# ProPrj_arm_can_tool_2026-04-18.net
KiCad netlist of a schematic drawn in EasyEDA Pro
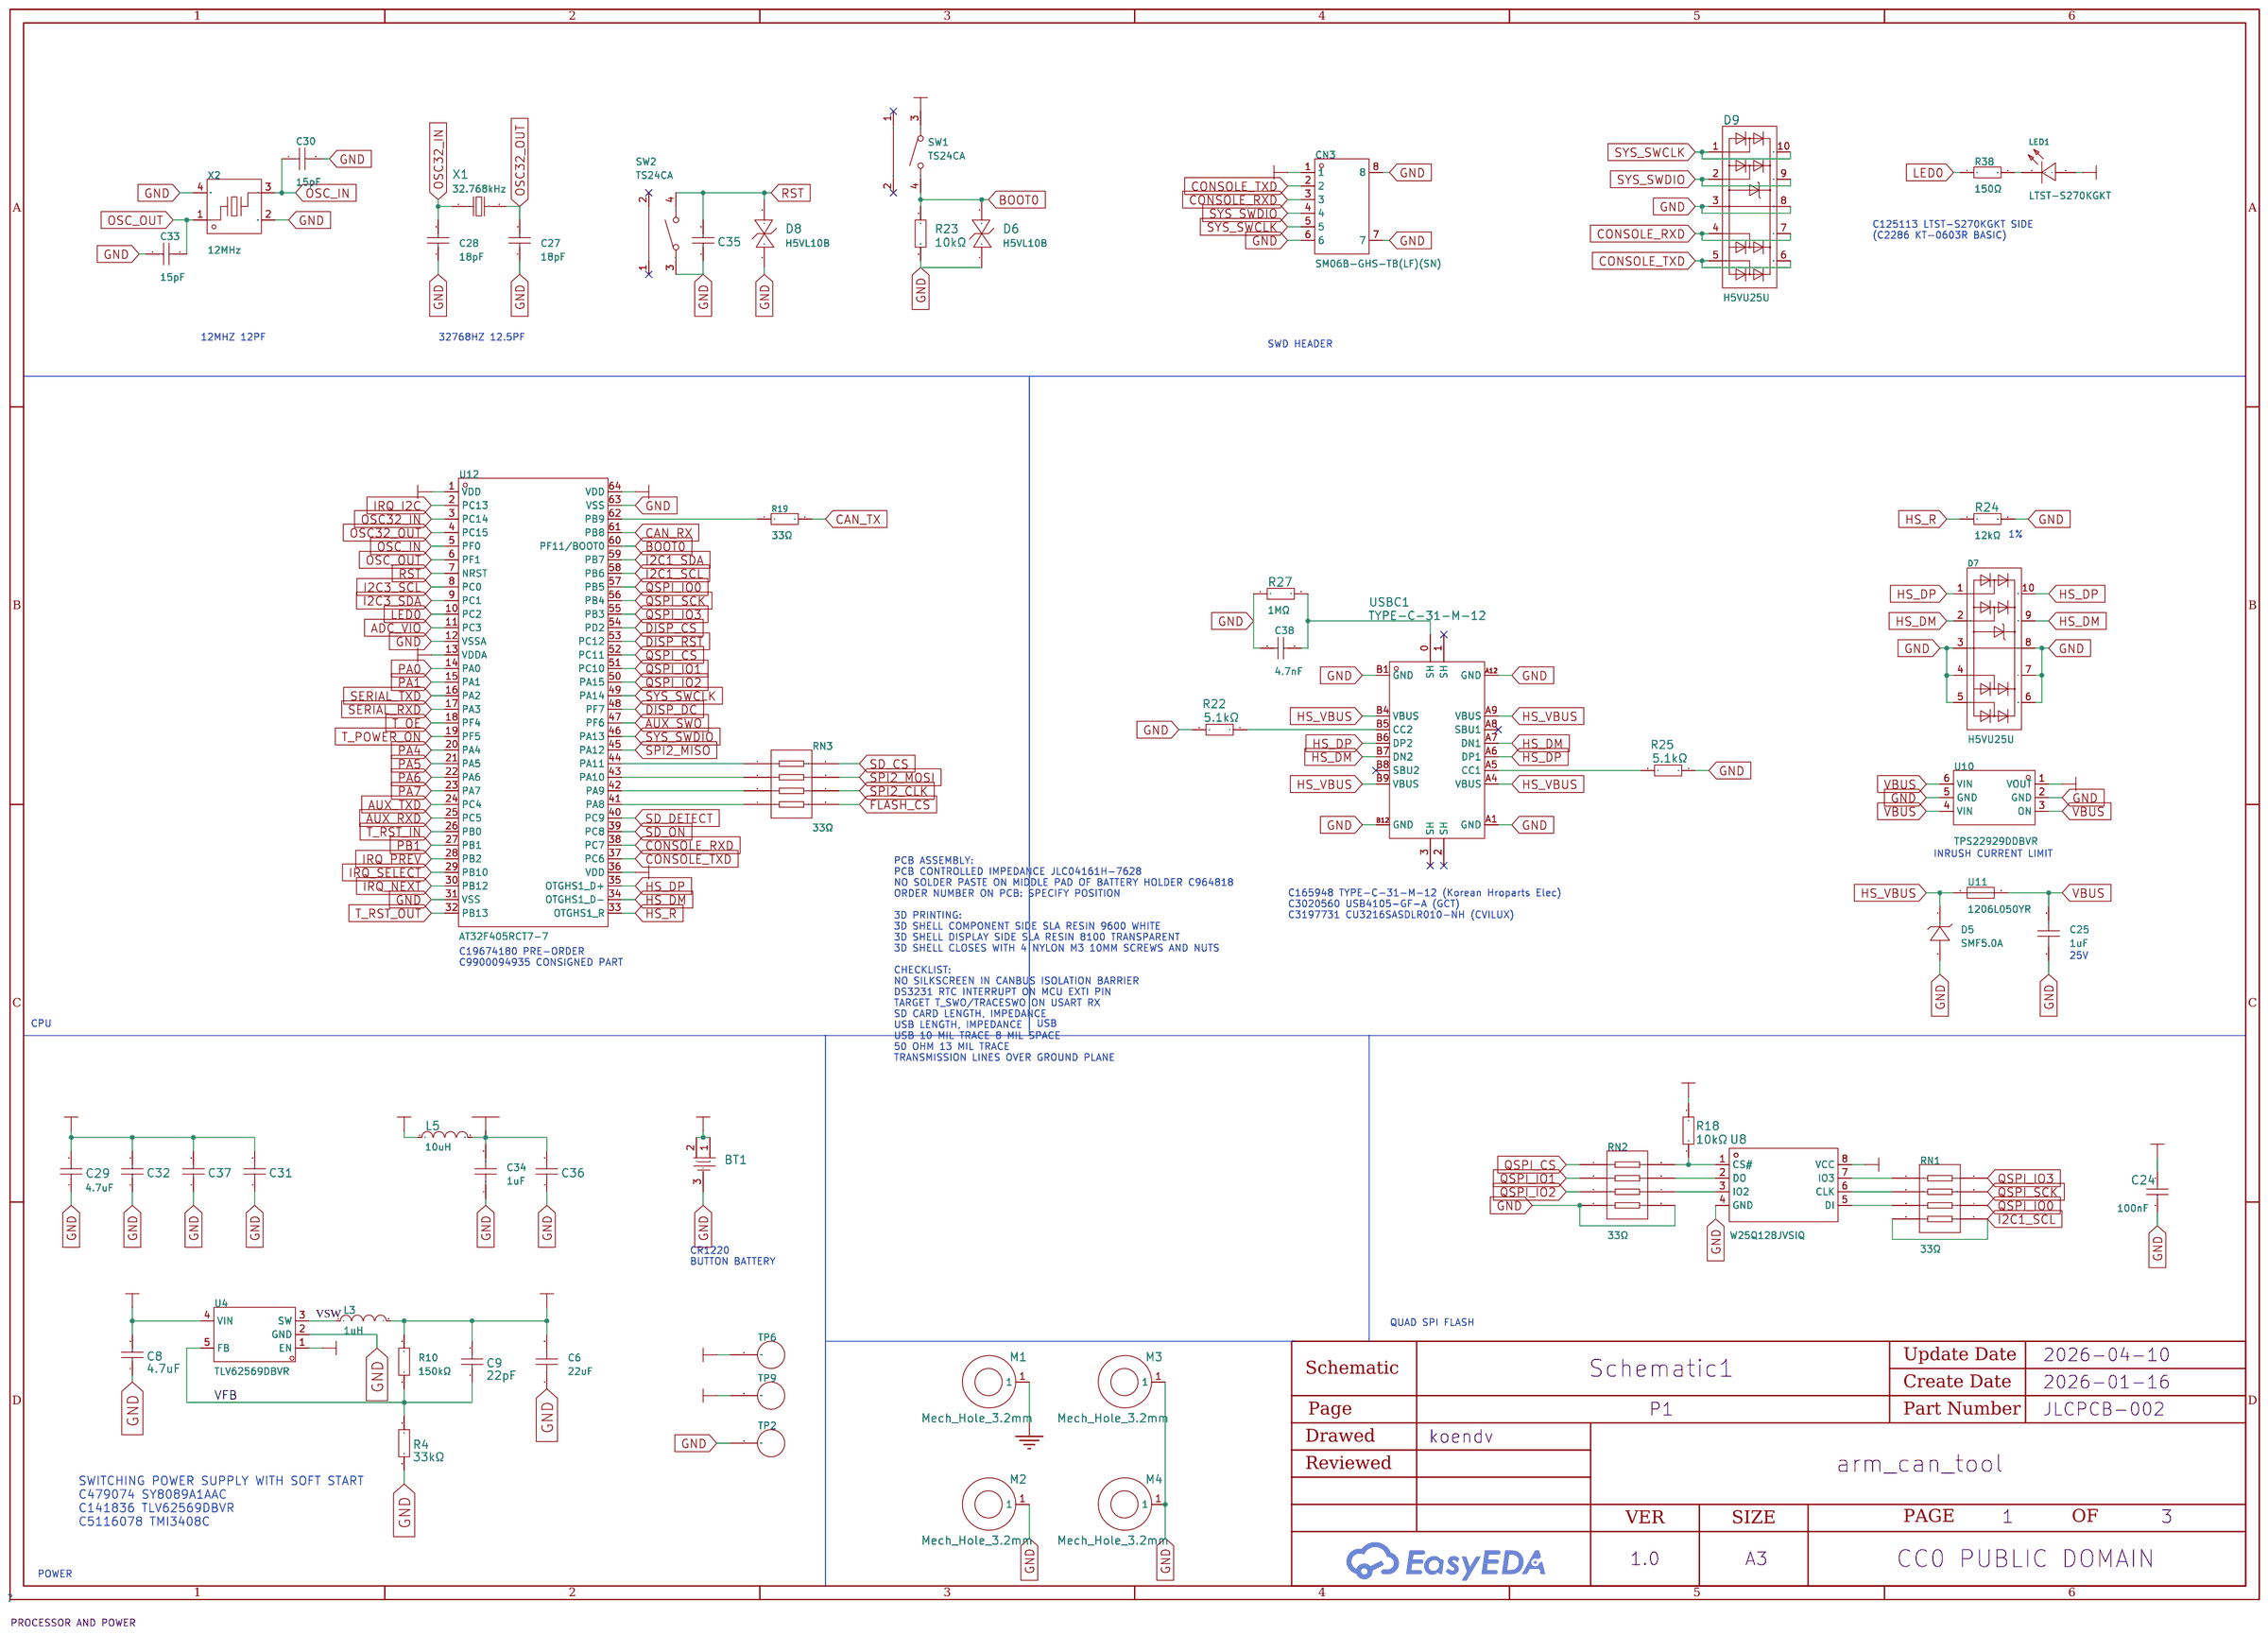
[diagram p0: P1]
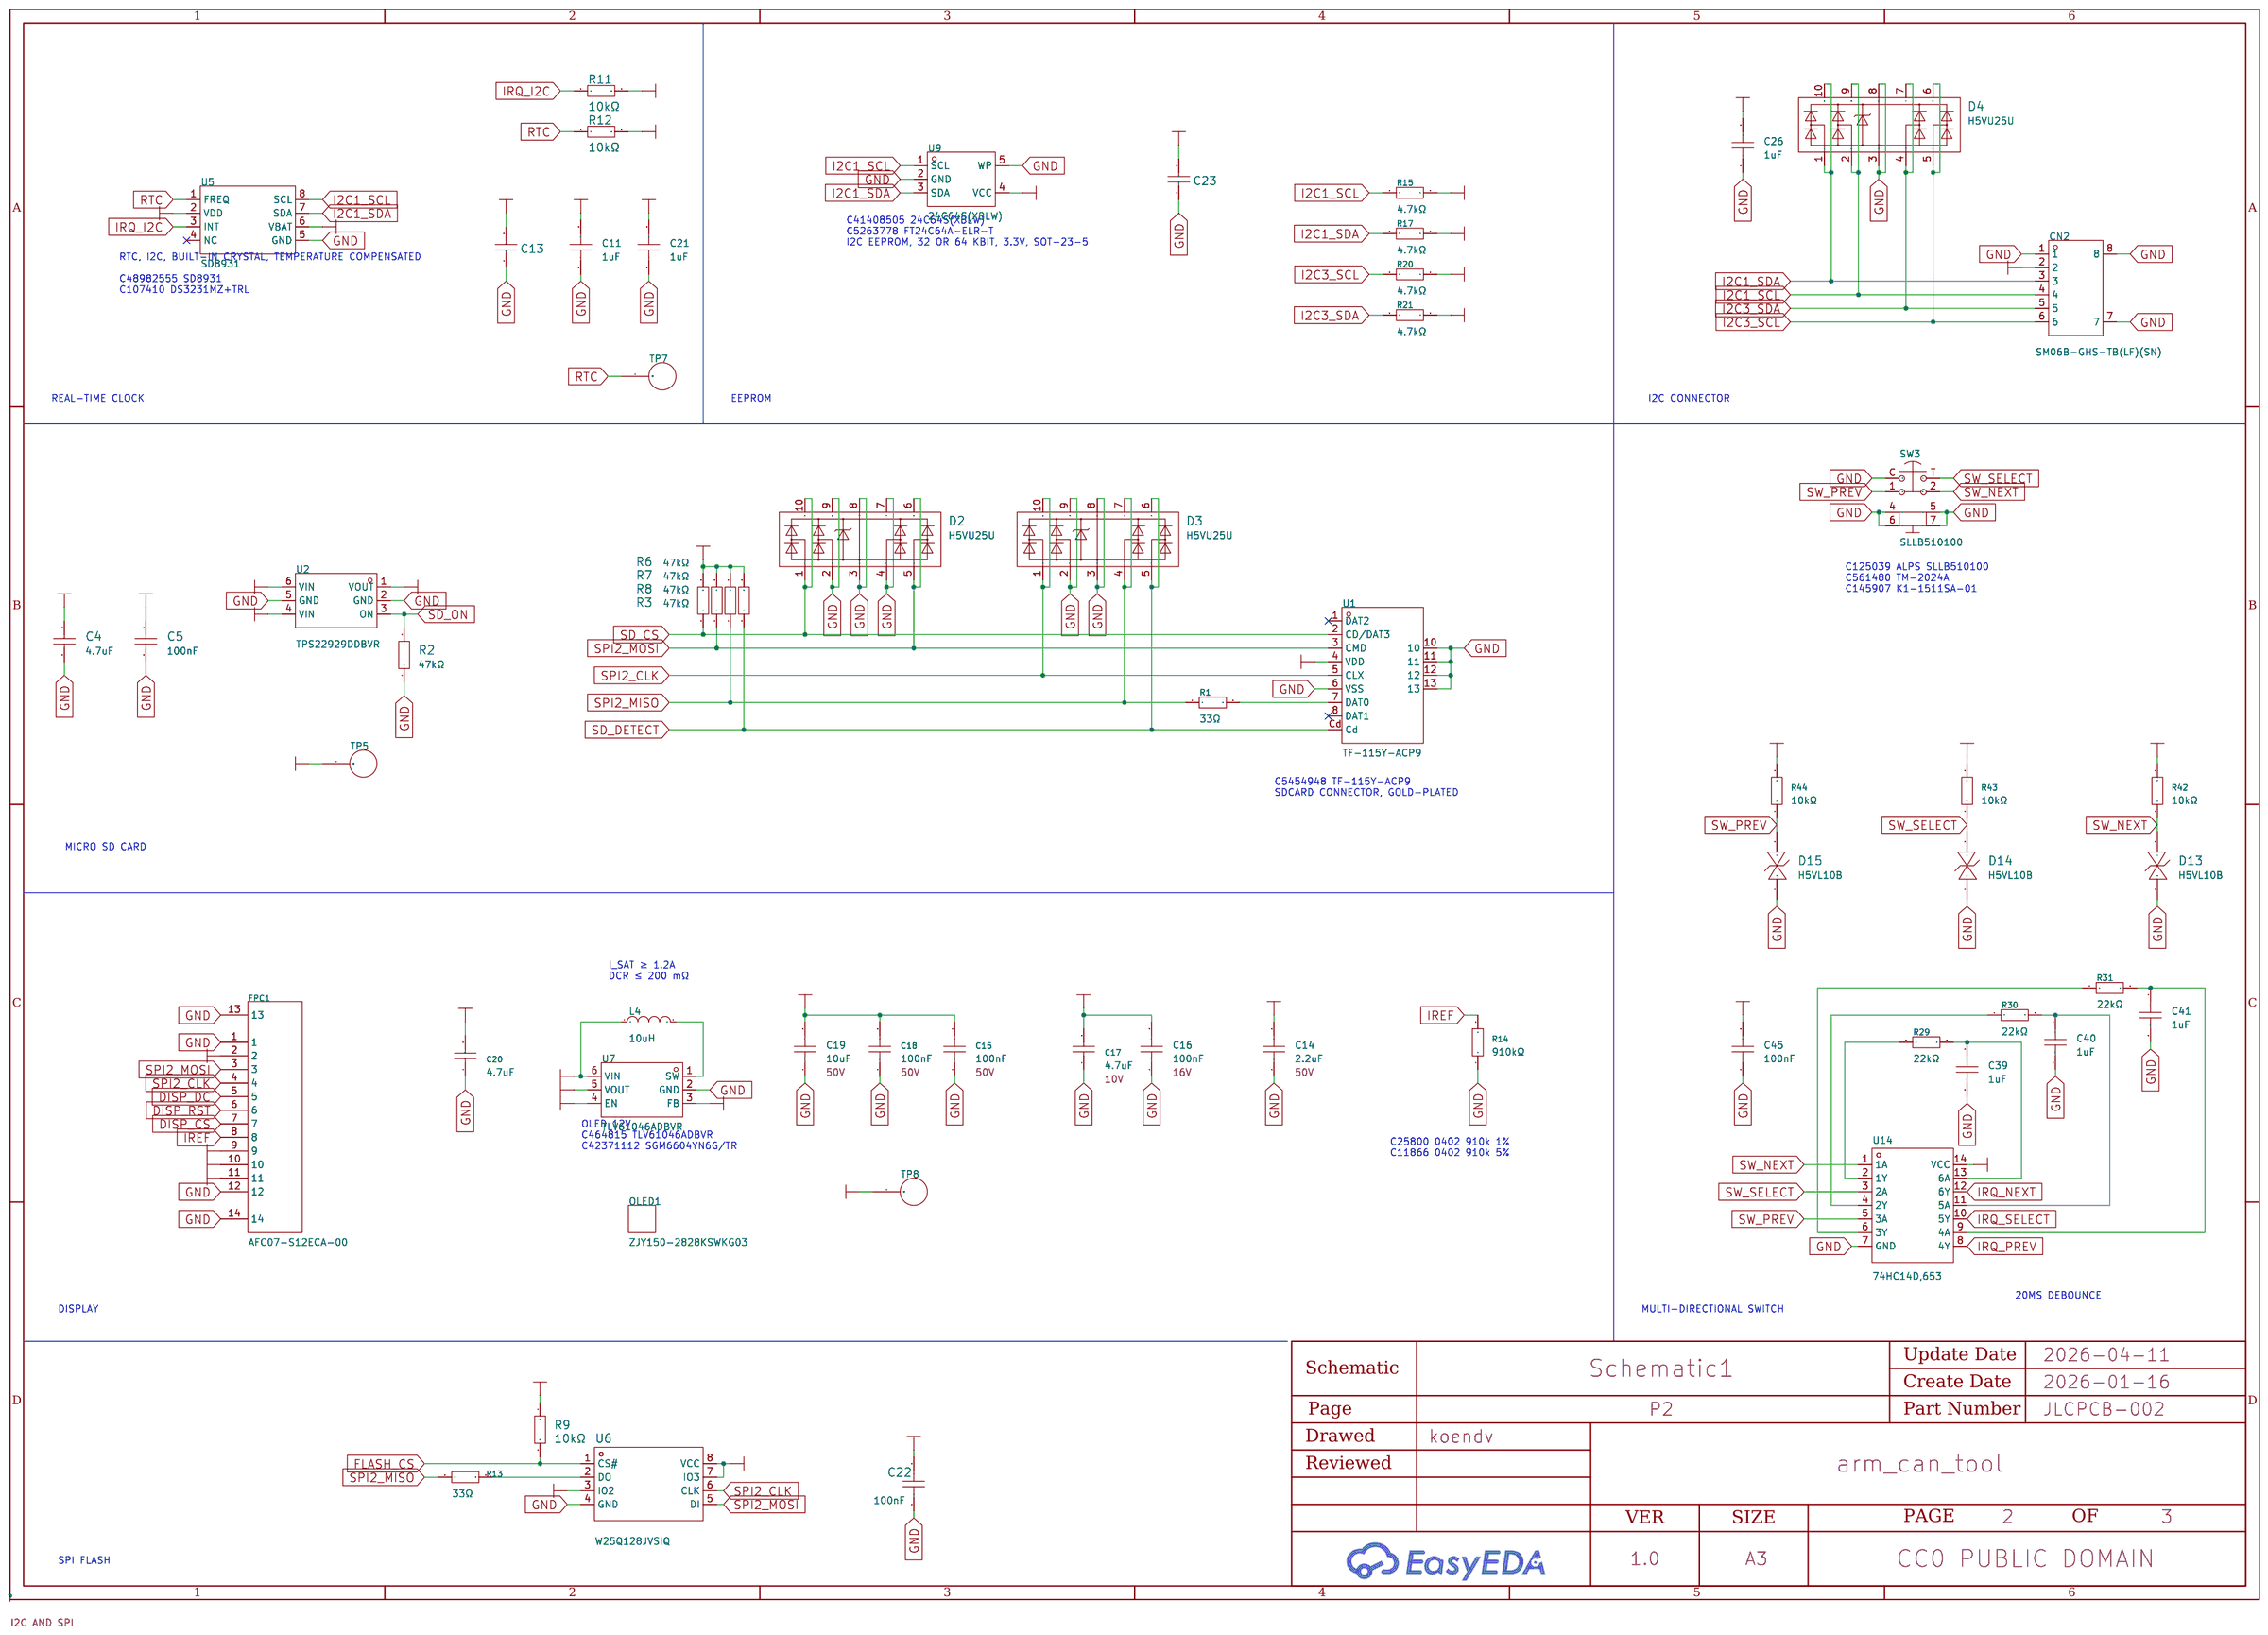
[diagram p1: P2]
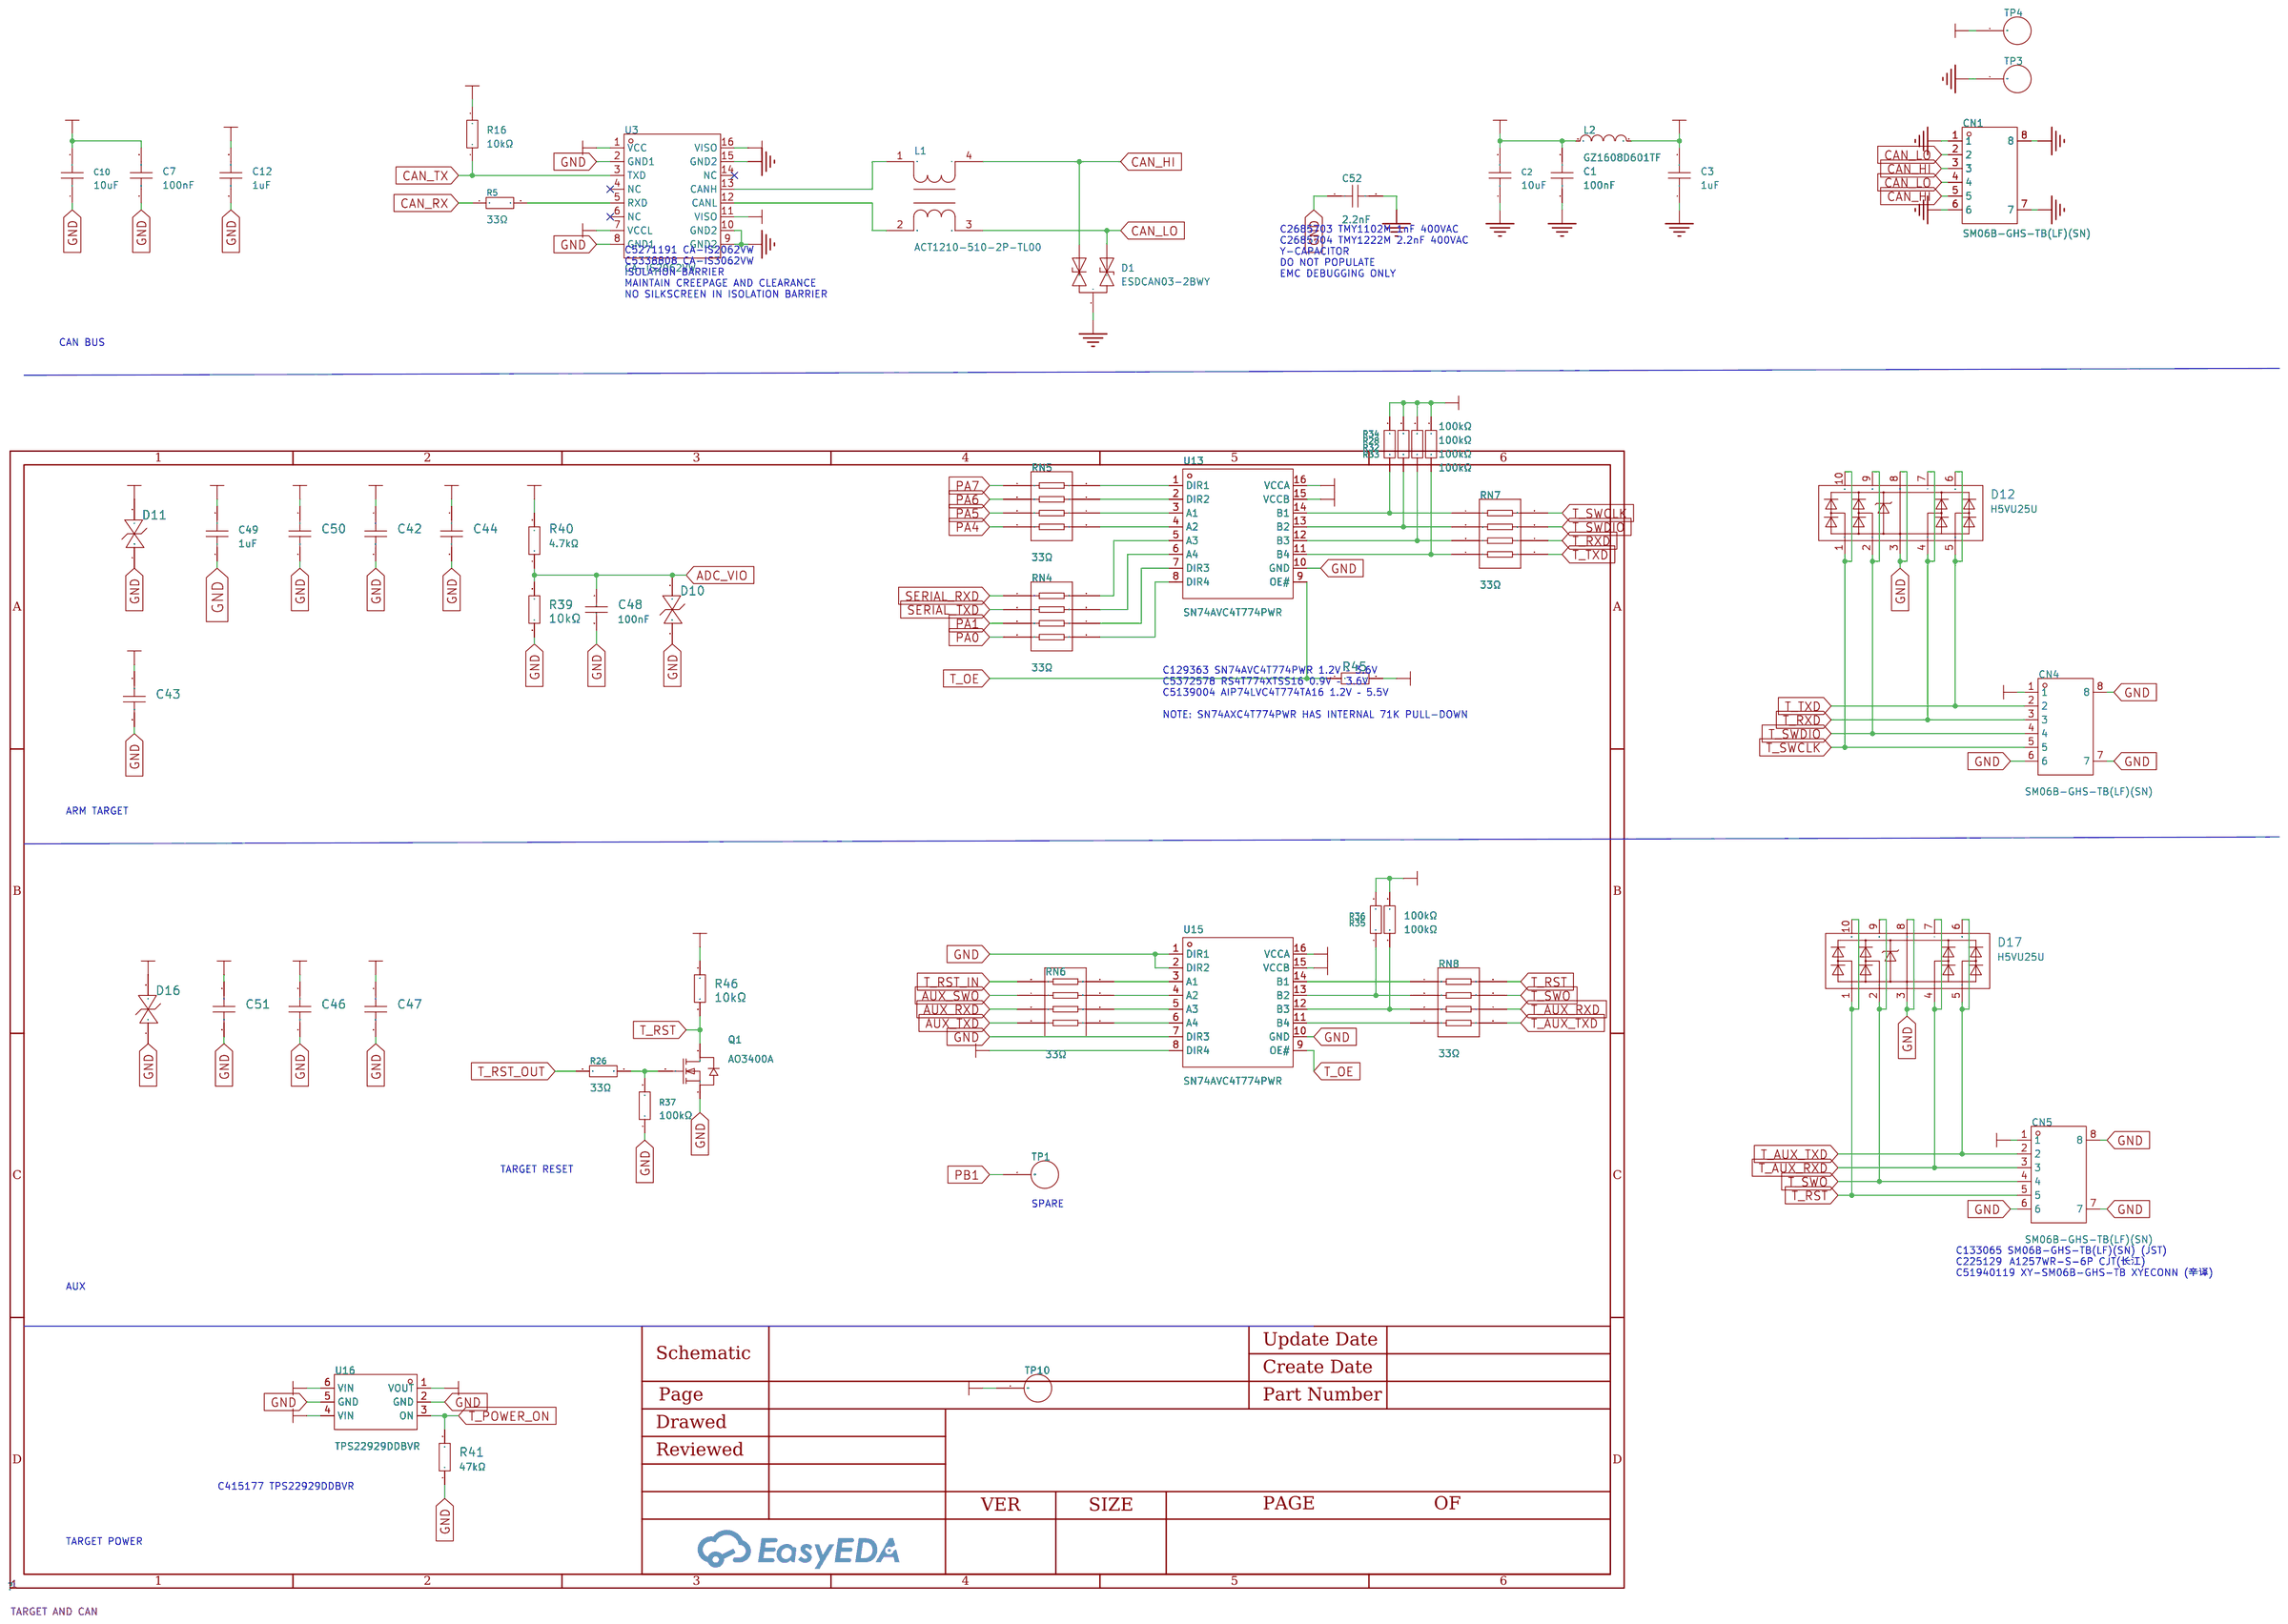
[diagram p2: P3]

(export (version "E")
  (design (tool "Eeschema 10.0.6"))
  (components
    (comp (ref "BT1")
      (value "MY-1220-03")
      (footprint "easyedapro:BAT-SMD_MY-1220-03")
      (fields (field (name "Manufacturer") "MYOUNG(美阳)"))
      (libsource (lib "easyedapro") (part "MY-1220-03"))
    )
    (comp (ref "C6")
      (value "22uF")
      (footprint "easyedapro:C0603")
      (fields
        (field (name "Manufacturer Part") "CL10A226MQ8NRNC")
        (field (name "Manufacturer") "SAMSUNG(三星)")
      )
      (libsource (lib "easyedapro") (part "CL10A226MQ8NRNC"))
    )
    (comp (ref "C8")
      (value "4.7uF")
      (footprint "easyedapro:C0603")
      (description "Capacitance:4.7uF Tolerance:±10% Tolerance:±10% Voltage Rating:16V Temperature Coefficient:X5R")
      (fields
        (field (name "Manufacturer Part") "CL10A475KO8NNNC")
        (field (name "Manufacturer") "SAMSUNG(三星)")
      )
      (libsource (lib "easyedapro") (part "4.7uF"))
    )
    (comp (ref "C9")
      (value "22pF")
      (footprint "easyedapro:C0402")
      (fields (field (name "Manufacturer Part") "0402CG220J500NT") (field (name "Manufacturer") "FH(风华)"))
      (libsource (lib "easyedapro") (part "22pF"))
    )
    (comp (ref "C24")
      (value "100nF")
      (footprint "easyedapro:C0402")
      (fields
        (field (name "Manufacturer Part") "CL05B104KO5NNNC")
        (field (name "Manufacturer") "SAMSUNG(三星)")
      )
      (libsource (lib "easyedapro") (part "CL05B104KO5NNNC"))
    )
    (comp (ref "C25")
      (value "1uF")
      (footprint "easyedapro:C0402")
      (fields
        (field (name "Manufacturer Part") "CL05A105KA5NQNC")
        (field (name "Manufacturer") "SAMSUNG(三星)")
      )
      (libsource (lib "easyedapro") (part "CL05A105KA5NQNC"))
    )
    (comp (ref "C27")
      (value "18pF")
      (footprint "easyedapro:C0402")
      (fields (field (name "Manufacturer Part") "0402CG180J500NT") (field (name "Manufacturer") "FH(风华)"))
      (libsource (lib "easyedapro") (part "0402CG180J500NT"))
    )
    (comp (ref "C28")
      (value "18pF")
      (footprint "easyedapro:C0402")
      (fields (field (name "Manufacturer Part") "0402CG180J500NT") (field (name "Manufacturer") "FH(风华)"))
      (libsource (lib "easyedapro") (part "0402CG180J500NT"))
    )
    (comp (ref "C29")
      (value "4.7uF")
      (footprint "easyedapro:C0402")
      (fields
        (field (name "Manufacturer Part") "CL05A475MP5NRNC")
        (field (name "Manufacturer") "SAMSUNG(三星)")
      )
      (libsource (lib "easyedapro") (part "CL05A475MP5NRNC"))
    )
    (comp (ref "C30")
      (value "15pF")
      (footprint "easyedapro:C0402")
      (fields (field (name "Manufacturer Part") "0402CG150J500NT") (field (name "Manufacturer") "FH(风华)"))
      (libsource (lib "easyedapro") (part "0402CG150J500NT"))
    )
    (comp (ref "C31")
      (value "100nF")
      (footprint "easyedapro:C0402_NEW")
      (fields
        (field (name "Manufacturer Part") "CL05B104KO5NNNC")
        (field (name "Manufacturer") "SAMSUNG(三星)")
      )
      (libsource (lib "easyedapro") (part "100nF"))
    )
    (comp (ref "C32")
      (value "100nF")
      (footprint "easyedapro:C0402_NEW")
      (fields
        (field (name "Manufacturer Part") "CL05B104KO5NNNC")
        (field (name "Manufacturer") "SAMSUNG(三星)")
      )
      (libsource (lib "easyedapro") (part "100nF"))
    )
    (comp (ref "C33")
      (value "15pF")
      (footprint "easyedapro:C0402")
      (fields (field (name "Manufacturer Part") "0402CG150J500NT") (field (name "Manufacturer") "FH(风华)"))
      (libsource (lib "easyedapro") (part "0402CG150J500NT"))
    )
    (comp (ref "C34")
      (value "1uF")
      (footprint "easyedapro:C0402")
      (fields
        (field (name "Manufacturer Part") "CL05A105KA5NQNC")
        (field (name "Manufacturer") "SAMSUNG(三星)")
      )
      (libsource (lib "easyedapro") (part "CL05A105KA5NQNC"))
    )
    (comp (ref "C35")
      (value "100nF")
      (footprint "easyedapro:C0402_NEW")
      (fields
        (field (name "Manufacturer Part") "CL05B104KO5NNNC")
        (field (name "Manufacturer") "SAMSUNG(三星)")
      )
      (libsource (lib "easyedapro") (part "100nF"))
    )
    (comp (ref "C36")
      (value "100nF")
      (footprint "easyedapro:C0402_NEW")
      (fields
        (field (name "Manufacturer Part") "CL05B104KO5NNNC")
        (field (name "Manufacturer") "SAMSUNG(三星)")
      )
      (libsource (lib "easyedapro") (part "100nF"))
    )
    (comp (ref "C37")
      (value "100nF")
      (footprint "easyedapro:C0402_NEW")
      (fields
        (field (name "Manufacturer Part") "CL05B104KO5NNNC")
        (field (name "Manufacturer") "SAMSUNG(三星)")
      )
      (libsource (lib "easyedapro") (part "100nF"))
    )
    (comp (ref "C38")
      (value "4.7nF")
      (footprint "easyedapro:C0402")
      (fields (field (name "Manufacturer Part") "0402B472K500NT") (field (name "Manufacturer") "FH(风华)"))
      (libsource (lib "easyedapro") (part "0402B472K500NT"))
    )
    (comp (ref "CN3")
      (value "SM06B-GHS-TB(LF)(SN)")
      (footprint "easyedapro:CONN-TH_SM06B-GHS-TB-LF-SN")
      (fields (field (name "Manufacturer") "JST"))
      (libsource (lib "easyedapro") (part "SM06B-GHS-TB(LF)(SN)"))
    )
    (comp (ref "D5")
      (value "SMF5.0A")
      (footprint "easyedapro:SOD-123FL_L2.7-W1.8-LS3.8-RD")
      (fields (field (name "Manufacturer") "R+O(宏嘉诚)"))
      (libsource (lib "easyedapro") (part "SMF5.0A_C19077497"))
    )
    (comp (ref "D6")
      (value "H5VL10B")
      (footprint "easyedapro:SOD-882_L1.0-W0.6-BI")
      (fields (field (name "Manufacturer") "宏迦橙"))
      (libsource (lib "easyedapro") (part "H5VL10B"))
    )
    (comp (ref "D7")
      (value "H5VU25U")
      (fields (field (name "Manufacturer") "宏迦橙"))
      (libsource (lib "easyedapro") (part "H5VU25U"))
    )
    (comp (ref "D8")
      (value "H5VL10B")
      (footprint "easyedapro:SOD-882_L1.0-W0.6-BI")
      (fields (field (name "Manufacturer") "宏迦橙"))
      (libsource (lib "easyedapro") (part "H5VL10B"))
    )
    (comp (ref "D9")
      (value "H5VU25U")
      (fields (field (name "Manufacturer") "宏迦橙"))
      (libsource (lib "easyedapro") (part "H5VU25U"))
    )
    (comp (ref "L3")
      (value "1uH")
      (footprint "easyedapro:IND-SMD_L2.5-W2.0-A")
      (description "Inductance: Tolerance:±20% Tolerance:±20% Rated Current:- DC Resistance (DCR):-")
      (fields (field (name "Manufacturer Part") "TFM252012ALM-1R0MTAA") (field (name "Manufacturer") "TDK"))
      (libsource (lib "easyedapro") (part "TFM252012ALM-1R0MTAA"))
    )
    (comp (ref "L5")
      (value "10uH")
      (footprint "easyedapro:L0603")
      (fields
        (field (name "Manufacturer Part") "SDFL1608S100KTF")
        (field (name "Manufacturer") "Sunlord(顺络)")
      )
      (libsource (lib "easyedapro") (part "SDFL1608S100KTF"))
    )
    (comp (ref "LED1")
      (value "LTST-S270KGKT")
      (footprint "easyedapro:LED-SMD_L1.7-W0.6-RD")
      (fields (field (name "Manufacturer") "LITEON(光宝)"))
      (libsource (lib "easyedapro") (part "LTST-S270KGKT"))
    )
    (comp (ref "M1")
      (value "Mech_Hole_3.2mm")
      (footprint "easyedapro:MECH_HOLE_3.2MM")
      (libsource (lib "easyedapro") (part "Mech_Hole_3.2mm"))
    )
    (comp (ref "M2")
      (value "Mech_Hole_3.2mm")
      (footprint "easyedapro:MECH_HOLE_3.2MM")
      (libsource (lib "easyedapro") (part "Mech_Hole_3.2mm"))
    )
    (comp (ref "M3")
      (value "Mech_Hole_3.2mm")
      (footprint "easyedapro:MECH_HOLE_3.2MM")
      (libsource (lib "easyedapro") (part "Mech_Hole_3.2mm"))
    )
    (comp (ref "M4")
      (value "Mech_Hole_3.2mm")
      (footprint "easyedapro:MECH_HOLE_3.2MM")
      (libsource (lib "easyedapro") (part "Mech_Hole_3.2mm"))
    )
    (comp (ref "R4")
      (value "33kΩ")
      (footprint "easyedapro:R0402")
      (fields
        (field (name "Manufacturer Part") "0402WGF3302TCE")
        (field (name "Manufacturer") "UNI-ROYAL(厚声)")
      )
      (libsource (lib "easyedapro") (part "33kΩ"))
    )
    (comp (ref "R10")
      (value "150kΩ")
      (footprint "easyedapro:R0402")
      (fields
        (field (name "Manufacturer Part") "0402WGF1503TCE")
        (field (name "Manufacturer") "UNI-ROYAL(厚声)")
      )
      (libsource (lib "easyedapro") (part "0402WGF1503TCE"))
    )
    (comp (ref "R18")
      (value "10kΩ")
      (footprint "easyedapro:R0402")
      (fields
        (field (name "Manufacturer Part") "0402WGF1002TCE")
        (field (name "Manufacturer") "UNI-ROYAL(厚声)")
      )
      (libsource (lib "easyedapro") (part "10kΩ"))
    )
    (comp (ref "R19")
      (value "33Ω")
      (footprint "easyedapro:R0402")
      (fields
        (field (name "Manufacturer Part") "0402WGF330JTCE")
        (field (name "Manufacturer") "UNI-ROYAL(厚声)")
      )
      (libsource (lib "easyedapro") (part "0402WGF330JTCE"))
    )
    (comp (ref "R22")
      (value "5.1kΩ")
      (footprint "easyedapro:R0402")
      (fields
        (field (name "Manufacturer Part") "0402WGF5101TCE")
        (field (name "Manufacturer") "UNI-ROYAL(厚声)")
      )
      (libsource (lib "easyedapro") (part "5.1kΩ"))
    )
    (comp (ref "R23")
      (value "10kΩ")
      (footprint "easyedapro:R0402")
      (fields
        (field (name "Manufacturer Part") "0402WGF1002TCE")
        (field (name "Manufacturer") "UNI-ROYAL(厚声)")
      )
      (libsource (lib "easyedapro") (part "10kΩ"))
    )
    (comp (ref "R24")
      (value "12kΩ")
      (footprint "easyedapro:R0402")
      (fields
        (field (name "Manufacturer Part") "0402WGF1202TCE")
        (field (name "Manufacturer") "UNI-ROYAL(厚声)")
      )
      (libsource (lib "easyedapro") (part "0402WGF1202TCE"))
    )
    (comp (ref "R25")
      (value "5.1kΩ")
      (footprint "easyedapro:R0402")
      (fields
        (field (name "Manufacturer Part") "0402WGF5101TCE")
        (field (name "Manufacturer") "UNI-ROYAL(厚声)")
      )
      (libsource (lib "easyedapro") (part "5.1kΩ"))
    )
    (comp (ref "R27")
      (value "1MΩ")
      (footprint "easyedapro:R0402")
      (fields
        (field (name "Manufacturer Part") "0402WGF1004TCE")
        (field (name "Manufacturer") "UNI-ROYAL(厚声)")
      )
      (libsource (lib "easyedapro") (part "0402WGF1004TCE"))
    )
    (comp (ref "R38")
      (value "150Ω")
      (footprint "easyedapro:R0402")
      (fields
        (field (name "Manufacturer Part") "0402WGF1500TCE")
        (field (name "Manufacturer") "UNI-ROYAL(厚声)")
      )
      (libsource (lib "easyedapro") (part "0402WGF1500TCE"))
    )
    (comp (ref "RN1")
      (value "33Ω")
      (footprint "easyedapro:RES-ARRAY-SMD_0402-8P-L2.0-W1.0-BL")
      (fields (field (name "Manufacturer Part") "YC124-FR-0733RL") (field (name "Manufacturer") "YAGEO(国巨)"))
      (libsource (lib "easyedapro") (part "YC124-FR-0733RL"))
    )
    (comp (ref "RN2")
      (value "33Ω")
      (footprint "easyedapro:RES-ARRAY-SMD_0402-8P-L2.0-W1.0-BL")
      (fields (field (name "Manufacturer Part") "YC124-FR-0733RL") (field (name "Manufacturer") "YAGEO(国巨)"))
      (libsource (lib "easyedapro") (part "YC124-FR-0733RL"))
    )
    (comp (ref "RN3")
      (value "33Ω")
      (footprint "easyedapro:RES-ARRAY-SMD_0402-8P-L2.0-W1.0-BL")
      (fields (field (name "Manufacturer Part") "YC124-FR-0733RL") (field (name "Manufacturer") "YAGEO(国巨)"))
      (libsource (lib "easyedapro") (part "YC124-FR-0733RL"))
    )
    (comp (ref "SW1")
      (value "TS24CA")
      (footprint "easyedapro:SW-SMD_TS24CA")
      (fields (field (name "Manufacturer") "SHOU HAN(首韩)"))
      (libsource (lib "easyedapro") (part "TS24CA"))
    )
    (comp (ref "SW2")
      (value "TS24CA")
      (footprint "easyedapro:SW-SMD_TS24CA")
      (fields (field (name "Manufacturer") "SHOU HAN(首韩)"))
      (libsource (lib "easyedapro") (part "TS24CA"))
    )
    (comp (ref "TP2")
      (value "~")
      (footprint "easyedapro:TEST PAD")
      (libsource (lib "easyedapro") (part "TEST PAD"))
    )
    (comp (ref "TP6")
      (value "~")
      (footprint "easyedapro:TEST PAD")
      (libsource (lib "easyedapro") (part "TEST PAD"))
    )
    (comp (ref "TP9")
      (value "~")
      (footprint "easyedapro:TEST PAD")
      (libsource (lib "easyedapro") (part "TEST PAD"))
    )
    (comp (ref "U4")
      (value "TLV62569DBVR")
      (footprint "easyedapro:SOT-23-5_L3.0-W1.7-P0.95-LS2.8-BR")
      (fields (field (name "Manufacturer") "TI(德州仪器)"))
      (libsource (lib "easyedapro") (part "TLV62569DBVR"))
    )
    (comp (ref "U8")
      (value "W25Q128JVSIQ")
      (footprint "easyedapro:SOIC-8_L5.3-W5.3-P1.27-LS8.0-BL")
      (fields (field (name "Manufacturer") "WINBOND(华邦)"))
      (libsource (lib "easyedapro") (part "W25Q128JVSIQTR"))
    )
    (comp (ref "U10")
      (value "TPS22929DDBVR")
      (footprint "easyedapro:SOT-23-6_L2.9-W1.6-P0.95-LS2.8-BL")
      (fields (field (name "Manufacturer") "TI(德州仪器)"))
      (libsource (lib "easyedapro") (part "TPS22929DDBVR"))
    )
    (comp (ref "U11")
      (value "1206L050YR")
      (footprint "easyedapro:F1206")
      (fields (field (name "Manufacturer") "Littelfuse(美国力特)"))
      (libsource (lib "easyedapro") (part "1206L050YR"))
    )
    (comp (ref "U12")
      (value "AT32F405RCT7-7")
      (footprint "easyedapro:LQFP-64_L7.0-W7.0-P0.40-LS9.0-TL")
      (fields (field (name "Manufacturer") "Artery(雅特力)"))
      (libsource (lib "easyedapro") (part "AT32F405RCT7-7"))
    )
    (comp (ref "USBC1")
      (value "TYPE-C-31-M-12")
      (footprint "easyedapro:USB-C_SMD-TYPE-C-31-M-12")
      (fields (field (name "Manufacturer") "韩国韩荣"))
      (libsource (lib "easyedapro") (part "TYPE-C-31-M-12"))
    )
    (comp (ref "X1")
      (value "32.768kHz")
      (footprint "easyedapro:FC-135R_L3.2-W1.5")
      (fields (field (name "Manufacturer Part") "Q13FC1350000400") (field (name "Manufacturer") "EPSON(爱普生)"))
      (libsource (lib "easyedapro") (part "Q13FC1350000400"))
    )
    (comp (ref "X2")
      (value "12MHz")
      (footprint "easyedapro:CRYSTAL-SMD_4P-L3.2-W2.5-BL")
      (fields
        (field (name "Manufacturer Part") "CJ13-120001210B20")
        (field (name "Manufacturer") "CJ(江苏长电/长晶)")
      )
      (libsource (lib "easyedapro") (part "CJ13-120001210B20"))
    )
    (comp (ref "C4")
      (value "4.7uF")
      (footprint "easyedapro:C0603")
      (description "Capacitance:4.7uF Tolerance:±10% Tolerance:±10% Voltage Rating:16V Temperature Coefficient:X5R")
      (fields
        (field (name "Manufacturer Part") "CL10A475KO8NNNC")
        (field (name "Manufacturer") "SAMSUNG(三星)")
      )
      (libsource (lib "easyedapro") (part "CL10A475KO8NNNC"))
    )
    (comp (ref "C5")
      (value "100nF")
      (footprint "easyedapro:C0402")
      (fields
        (field (name "Manufacturer Part") "CL05B104KO5NNNC")
        (field (name "Manufacturer") "SAMSUNG(三星)")
      )
      (libsource (lib "") (part "CL05B104KO5NNNC_1"))
    )
    (comp (ref "C11")
      (value "1uF")
      (fields
        (field (name "Manufacturer Part") "CL05A105KA5NQNC")
        (field (name "Manufacturer") "SAMSUNG(三星)")
      )
      (libsource (lib "easyedapro") (part "CL05A105KA5NQNC"))
    )
    (comp (ref "C13")
      (value "100nF")
      (footprint "easyedapro:C0402_NEW")
      (fields
        (field (name "Manufacturer Part") "CL05B104KO5NNNC")
        (field (name "Manufacturer") "SAMSUNG(三星)")
      )
      (libsource (lib "easyedapro") (part "100nF"))
    )
    (comp (ref "C14")
      (value "2.2uF")
      (footprint "easyedapro:C0805")
      (fields
        (field (name "Manufacturer Part") "CL21A225KBQNNNE")
        (field (name "Manufacturer") "SAMSUNG(三星)")
        (field (name "Voltage Rated") "50V")
      )
      (libsource (lib "easyedapro") (part "CL21A225KBQNNNE"))
    )
    (comp (ref "C15")
      (value "100nF")
      (footprint "easyedapro:C0603")
      (fields
        (field (name "Manufacturer Part") "CC0603KRX7R9BB104")
        (field (name "Manufacturer") "YAGEO(国巨)")
        (field (name "Voltage Rated") "50V")
      )
      (libsource (lib "easyedapro") (part "CC0603KRX7R9BB104"))
    )
    (comp (ref "C16")
      (value "100nF")
      (fields
        (field (name "Manufacturer Part") "CL05B104KO5NNNC")
        (field (name "Manufacturer") "SAMSUNG(三星)")
        (field (name "Voltage Rated") "16V")
      )
      (libsource (lib "easyedapro") (part "CL05B104KO5NNNC"))
    )
    (comp (ref "C17")
      (value "4.7uF")
      (footprint "easyedapro:C0402")
      (fields
        (field (name "Manufacturer Part") "CL05A475MP5NRNC")
        (field (name "Manufacturer") "SAMSUNG(三星)")
        (field (name "Voltage Rated") "10V")
      )
      (libsource (lib "easyedapro") (part "CL05A475MP5NRNC"))
    )
    (comp (ref "C18")
      (value "100nF")
      (footprint "easyedapro:C0603")
      (fields
        (field (name "Manufacturer Part") "CC0603KRX7R9BB104")
        (field (name "Manufacturer") "YAGEO(国巨)")
        (field (name "Voltage Rated") "50V")
      )
      (libsource (lib "easyedapro") (part "CC0603KRX7R9BB104"))
    )
    (comp (ref "C19")
      (value "10uF")
      (footprint "easyedapro:C0805")
      (fields
        (field (name "Manufacturer Part") "GRM21BR61H106KE43L")
        (field (name "Manufacturer") "muRata(村田)")
        (field (name "Voltage Rated") "50V")
      )
      (libsource (lib "easyedapro") (part "GRM21BR61H106KE43L"))
    )
    (comp (ref "C20")
      (value "4.7uF")
      (footprint "easyedapro:C0402")
      (fields
        (field (name "Manufacturer Part") "CL05A475MP5NRNC")
        (field (name "Manufacturer") "SAMSUNG(三星)")
      )
      (libsource (lib "easyedapro") (part "CL05A475MP5NRNC"))
    )
    (comp (ref "C21")
      (value "1uF")
      (fields
        (field (name "Manufacturer Part") "CL05A105KA5NQNC")
        (field (name "Manufacturer") "SAMSUNG(三星)")
      )
      (libsource (lib "easyedapro") (part "CL05A105KA5NQNC"))
    )
    (comp (ref "C22")
      (value "100nF")
      (fields
        (field (name "Manufacturer Part") "CL05B104KO5NNNC")
        (field (name "Manufacturer") "SAMSUNG(三星)")
      )
      (libsource (lib "easyedapro") (part "CL05B104KO5NNNC"))
    )
    (comp (ref "C23")
      (value "100nF")
      (footprint "easyedapro:C0402_NEW")
      (fields
        (field (name "Manufacturer Part") "CL05B104KO5NNNC")
        (field (name "Manufacturer") "SAMSUNG(三星)")
      )
      (libsource (lib "easyedapro") (part "100nF"))
    )
    (comp (ref "C26")
      (value "1uF")
      (fields
        (field (name "Manufacturer Part") "CL05A105KA5NQNC")
        (field (name "Manufacturer") "SAMSUNG(三星)")
      )
      (libsource (lib "easyedapro") (part "CL05A105KA5NQNC"))
    )
    (comp (ref "C39")
      (value "1uF")
      (footprint "easyedapro:C0402")
      (fields
        (field (name "Manufacturer Part") "CL05A105KA5NQNC")
        (field (name "Manufacturer") "SAMSUNG(三星)")
      )
      (libsource (lib "easyedapro") (part "CL05A105KA5NQNC"))
    )
    (comp (ref "C40")
      (value "1uF")
      (footprint "easyedapro:C0402")
      (fields
        (field (name "Manufacturer Part") "CL05A105KA5NQNC")
        (field (name "Manufacturer") "SAMSUNG(三星)")
      )
      (libsource (lib "easyedapro") (part "CL05A105KA5NQNC"))
    )
    (comp (ref "C41")
      (value "1uF")
      (footprint "easyedapro:C0402")
      (fields
        (field (name "Manufacturer Part") "CL05A105KA5NQNC")
        (field (name "Manufacturer") "SAMSUNG(三星)")
      )
      (libsource (lib "easyedapro") (part "CL05A105KA5NQNC"))
    )
    (comp (ref "C45")
      (value "100nF")
      (fields
        (field (name "Manufacturer Part") "CL05B104KO5NNNC")
        (field (name "Manufacturer") "SAMSUNG(三星)")
      )
      (libsource (lib "easyedapro") (part "CL05B104KO5NNNC"))
    )
    (comp (ref "CN2")
      (value "SM06B-GHS-TB(LF)(SN)")
      (footprint "easyedapro:CONN-TH_SM06B-GHS-TB-LF-SN")
      (fields (field (name "Manufacturer") "JST"))
      (libsource (lib "easyedapro") (part "SM06B-GHS-TB(LF)(SN)"))
    )
    (comp (ref "D2")
      (value "H5VU25U")
      (fields (field (name "Manufacturer") "宏迦橙"))
      (libsource (lib "easyedapro") (part "H5VU25U"))
    )
    (comp (ref "D3")
      (value "H5VU25U")
      (fields (field (name "Manufacturer") "宏迦橙"))
      (libsource (lib "easyedapro") (part "H5VU25U"))
    )
    (comp (ref "D4")
      (value "H5VU25U")
      (fields (field (name "Manufacturer") "宏迦橙"))
      (libsource (lib "easyedapro") (part "H5VU25U"))
    )
    (comp (ref "D13")
      (value "H5VL10B")
      (footprint "easyedapro:SOD-882_L1.0-W0.6-BI")
      (fields (field (name "Manufacturer") "宏迦橙"))
      (libsource (lib "easyedapro") (part "H5VL10B"))
    )
    (comp (ref "D14")
      (value "H5VL10B")
      (footprint "easyedapro:SOD-882_L1.0-W0.6-BI")
      (fields (field (name "Manufacturer") "宏迦橙"))
      (libsource (lib "easyedapro") (part "H5VL10B"))
    )
    (comp (ref "D15")
      (value "H5VL10B")
      (footprint "easyedapro:SOD-882_L1.0-W0.6-BI")
      (fields (field (name "Manufacturer") "宏迦橙"))
      (libsource (lib "easyedapro") (part "H5VL10B"))
    )
    (comp (ref "FPC1")
      (value "AFC07-S12ECA-00")
      (footprint "easyedapro:FPC-SMD_12P-P0.50_AFC07-S12ECA-00")
      (fields (field (name "Manufacturer") "JS(钜硕电子)"))
      (libsource (lib "easyedapro") (part "AFC07-S12ECA-00"))
    )
    (comp (ref "L4")
      (value "10uH")
      (footprint "easyedapro:IND-SMD_L4.1-W4.1_FTC404020S")
      (fields
        (field (name "Manufacturer Part") "FTC404020S100MGCA")
        (field (name "Manufacturer") "cjiang(长江微电)")
      )
      (libsource (lib "easyedapro") (part "FTC404020S100MGCA"))
    )
    (comp (ref "OLED1")
      (value "ZJY150-2828KSWKG03")
      (footprint "easyedapro:OLED-ZJY150-2828KSWKG03")
      (fields (field (name "Manufacturer") "Zhengzhou Zhongjingyuan(中景园)"))
      (libsource (lib "easyedapro") (part "OLED-ZJY150-2828KSWKG03"))
    )
    (comp (ref "R1")
      (value "33Ω")
      (footprint "easyedapro:R0402")
      (fields
        (field (name "Manufacturer Part") "0402WGF330JTCE")
        (field (name "Manufacturer") "UNI-ROYAL(厚声)")
      )
      (libsource (lib "easyedapro") (part "0402WGF330JTCE"))
    )
    (comp (ref "R2")
      (value "47kΩ")
      (footprint "easyedapro:R0402")
      (fields
        (field (name "Manufacturer Part") "0402WGF4702TCE")
        (field (name "Manufacturer") "UNI-ROYAL(厚声)")
      )
      (libsource (lib "easyedapro") (part "0402WGF4702TCE"))
    )
    (comp (ref "R3")
      (value "47kΩ")
      (footprint "easyedapro:R0402")
      (fields
        (field (name "Manufacturer Part") "0402WGF4702TCE")
        (field (name "Manufacturer") "UNI-ROYAL(厚声)")
      )
      (libsource (lib "easyedapro") (part "0402WGF4702TCE"))
    )
    (comp (ref "R6")
      (value "47kΩ")
      (footprint "easyedapro:R0402")
      (fields
        (field (name "Manufacturer Part") "0402WGF4702TCE")
        (field (name "Manufacturer") "UNI-ROYAL(厚声)")
      )
      (libsource (lib "easyedapro") (part "0402WGF4702TCE"))
    )
    (comp (ref "R7")
      (value "47kΩ")
      (footprint "easyedapro:R0402")
      (fields
        (field (name "Manufacturer Part") "0402WGF4702TCE")
        (field (name "Manufacturer") "UNI-ROYAL(厚声)")
      )
      (libsource (lib "easyedapro") (part "0402WGF4702TCE"))
    )
    (comp (ref "R8")
      (value "47kΩ")
      (footprint "easyedapro:R0402")
      (fields
        (field (name "Manufacturer Part") "0402WGF4702TCE")
        (field (name "Manufacturer") "UNI-ROYAL(厚声)")
      )
      (libsource (lib "easyedapro") (part "0402WGF4702TCE"))
    )
    (comp (ref "R9")
      (value "10kΩ")
      (footprint "easyedapro:R0402")
      (fields
        (field (name "Manufacturer Part") "0402WGF1002TCE")
        (field (name "Manufacturer") "UNI-ROYAL(厚声)")
      )
      (libsource (lib "easyedapro") (part "10kΩ"))
    )
    (comp (ref "R11")
      (value "10kΩ")
      (footprint "easyedapro:R0402")
      (fields
        (field (name "Manufacturer Part") "0402WGF1002TCE")
        (field (name "Manufacturer") "UNI-ROYAL(厚声)")
      )
      (libsource (lib "easyedapro") (part "10kΩ"))
    )
    (comp (ref "R12")
      (value "10kΩ")
      (footprint "easyedapro:R0402")
      (fields
        (field (name "Manufacturer Part") "0402WGF1002TCE")
        (field (name "Manufacturer") "UNI-ROYAL(厚声)")
      )
      (libsource (lib "easyedapro") (part "10kΩ"))
    )
    (comp (ref "R13")
      (value "33Ω")
      (footprint "easyedapro:R0402")
      (fields
        (field (name "Manufacturer Part") "0402WGF330JTCE")
        (field (name "Manufacturer") "UNI-ROYAL(厚声)")
      )
      (libsource (lib "easyedapro") (part "0402WGF330JTCE"))
    )
    (comp (ref "R14")
      (value "910kΩ")
      (footprint "easyedapro:R0402")
      (fields
        (field (name "Manufacturer Part") "0402WGF9103TCE")
        (field (name "Manufacturer") "UNI-ROYAL(厚声)")
      )
      (libsource (lib "easyedapro") (part "0402WGF9103TCE"))
    )
    (comp (ref "R15")
      (value "4.7kΩ")
      (footprint "easyedapro:R0402")
      (fields
        (field (name "Manufacturer Part") "0402WGF4701TCE")
        (field (name "Manufacturer") "UNI-ROYAL(厚声)")
      )
      (libsource (lib "easyedapro") (part "0402WGF4701TCE"))
    )
    (comp (ref "R17")
      (value "4.7kΩ")
      (footprint "easyedapro:R0402")
      (fields
        (field (name "Manufacturer Part") "0402WGF4701TCE")
        (field (name "Manufacturer") "UNI-ROYAL(厚声)")
      )
      (libsource (lib "easyedapro") (part "0402WGF4701TCE"))
    )
    (comp (ref "R20")
      (value "4.7kΩ")
      (footprint "easyedapro:R0402")
      (fields
        (field (name "Manufacturer Part") "0402WGF4701TCE")
        (field (name "Manufacturer") "UNI-ROYAL(厚声)")
      )
      (libsource (lib "easyedapro") (part "0402WGF4701TCE"))
    )
    (comp (ref "R21")
      (value "4.7kΩ")
      (footprint "easyedapro:R0402")
      (fields
        (field (name "Manufacturer Part") "0402WGF4701TCE")
        (field (name "Manufacturer") "UNI-ROYAL(厚声)")
      )
      (libsource (lib "easyedapro") (part "0402WGF4701TCE"))
    )
    (comp (ref "R29")
      (value "22kΩ")
      (footprint "easyedapro:R0402")
      (fields
        (field (name "Manufacturer Part") "0402WGF2202TCE")
        (field (name "Manufacturer") "UNI-ROYAL(厚声)")
      )
      (libsource (lib "easyedapro") (part "0402WGF2202TCE"))
    )
    (comp (ref "R30")
      (value "22kΩ")
      (footprint "easyedapro:R0402")
      (fields
        (field (name "Manufacturer Part") "0402WGF2202TCE")
        (field (name "Manufacturer") "UNI-ROYAL(厚声)")
      )
      (libsource (lib "easyedapro") (part "0402WGF2202TCE"))
    )
    (comp (ref "R31")
      (value "22kΩ")
      (footprint "easyedapro:R0402")
      (fields
        (field (name "Manufacturer Part") "0402WGF2202TCE")
        (field (name "Manufacturer") "UNI-ROYAL(厚声)")
      )
      (libsource (lib "easyedapro") (part "0402WGF2202TCE"))
    )
    (comp (ref "R42")
      (value "10kΩ")
      (footprint "easyedapro:R0402")
      (fields
        (field (name "Manufacturer Part") "0402WGF1002TCE")
        (field (name "Manufacturer") "UNI-ROYAL(厚声)")
      )
      (libsource (lib "easyedapro") (part "0402WGF1002TCE"))
    )
    (comp (ref "R43")
      (value "10kΩ")
      (footprint "easyedapro:R0402")
      (fields
        (field (name "Manufacturer Part") "0402WGF1002TCE")
        (field (name "Manufacturer") "UNI-ROYAL(厚声)")
      )
      (libsource (lib "easyedapro") (part "0402WGF1002TCE"))
    )
    (comp (ref "R44")
      (value "10kΩ")
      (footprint "easyedapro:R0402")
      (fields
        (field (name "Manufacturer Part") "0402WGF1002TCE")
        (field (name "Manufacturer") "UNI-ROYAL(厚声)")
      )
      (libsource (lib "easyedapro") (part "0402WGF1002TCE"))
    )
    (comp (ref "SW3")
      (value "SLLB510100")
      (footprint "easyedapro:SW-SMD_SLLB510100")
      (fields (field (name "Manufacturer") "ALPSALPINE(阿尔卑斯阿尔派)"))
      (libsource (lib "easyedapro") (part "SLLB510100"))
    )
    (comp (ref "TP5")
      (value "~")
      (footprint "easyedapro:TEST PAD")
      (libsource (lib "easyedapro") (part "TEST PAD"))
    )
    (comp (ref "TP7")
      (value "~")
      (footprint "easyedapro:TEST PAD")
      (libsource (lib "easyedapro") (part "TEST PAD"))
    )
    (comp (ref "TP8")
      (value "~")
      (footprint "easyedapro:TEST PAD")
      (libsource (lib "easyedapro") (part "TEST PAD"))
    )
    (comp (ref "U1")
      (value "TF-115Y-ACP9")
      (footprint "easyedapro:SIM-SMD_TF-115Y-BCP9")
      (fields (field (name "Manufacturer") "XUNPU(讯普)"))
      (libsource (lib "easyedapro") (part "TF-115Y-ACP9"))
    )
    (comp (ref "U2")
      (value "TPS22929DDBVR")
      (footprint "easyedapro:SOT-23-6_L2.9-W1.6-P0.95-LS2.8-BL")
      (fields (field (name "Manufacturer") "TI(德州仪器)"))
      (libsource (lib "easyedapro") (part "TPS22929DDBVR"))
    )
    (comp (ref "U5")
      (value "SD8931")
      (footprint "easyedapro:SOP-8_L4.9-W3.9-P1.27-LS6.0-BL-1")
      (fields (field (name "Manufacturer") "WAVE(兴威帆电子)"))
      (libsource (lib "easyedapro") (part "SD8931"))
    )
    (comp (ref "U6")
      (value "W25Q128JVSIQ")
      (fields (field (name "Manufacturer") "WINBOND(华邦)"))
      (libsource (lib "easyedapro") (part "W25Q128JVSIQTR"))
    )
    (comp (ref "U7")
      (value "TLV61046ADBVR")
      (footprint "easyedapro:SOT-23-6_L2.9-W1.6-P0.95-LS2.8-BL")
      (fields (field (name "Manufacturer") "TI(德州仪器)"))
      (libsource (lib "easyedapro") (part "TLV61046ADBVR"))
    )
    (comp (ref "U9")
      (value "24C64S(XBLW)")
      (footprint "easyedapro:SOT-23-5_L2.9-W1.6-P0.95-LS2.8-BR")
      (fields (field (name "Manufacturer") "XBLW(芯伯乐)"))
      (libsource (lib "easyedapro") (part "24C64S(XBLW)"))
    )
    (comp (ref "U14")
      (value "74HC14D,653")
      (footprint "easyedapro:SOIC-14_L8.7-W3.9-P1.27-LS6.0-BL")
      (fields (field (name "Manufacturer") "Nexperia(安世)"))
      (libsource (lib "easyedapro") (part "74HC14D,653"))
    )
    (comp (ref "C1")
      (value "100nF")
      (footprint "easyedapro:C0603")
      (fields
        (field (name "Manufacturer Part") "CC0603KRX7R9BB104")
        (field (name "Manufacturer") "YAGEO(国巨)")
      )
      (libsource (lib "easyedapro") (part "CC0603KRX7R9BB104"))
    )
    (comp (ref "C2")
      (value "10uF")
      (footprint "easyedapro:C0603")
      (fields
        (field (name "Manufacturer Part") "CL10A106MA8NRNC")
        (field (name "Manufacturer") "SAMSUNG(三星)")
      )
      (libsource (lib "easyedapro") (part "CL10A106MA8NRNC"))
    )
    (comp (ref "C3")
      (value "1uF")
      (footprint "easyedapro:C0603")
      (fields
        (field (name "Manufacturer Part") "CL10A105KB8NNNC")
        (field (name "Manufacturer") "SAMSUNG(三星)")
      )
      (libsource (lib "easyedapro") (part "CL10A105KB8NNNC"))
    )
    (comp (ref "C7")
      (value "100nF")
      (footprint "easyedapro:C0603")
      (fields
        (field (name "Manufacturer Part") "CC0603KRX7R9BB104")
        (field (name "Manufacturer") "YAGEO(国巨)")
      )
      (libsource (lib "easyedapro") (part "CC0603KRX7R9BB104"))
    )
    (comp (ref "C10")
      (value "10uF")
      (footprint "easyedapro:C0603")
      (fields
        (field (name "Manufacturer Part") "CL10A106MA8NRNC")
        (field (name "Manufacturer") "SAMSUNG(三星)")
      )
      (libsource (lib "easyedapro") (part "CL10A106MA8NRNC"))
    )
    (comp (ref "C12")
      (value "1uF")
      (footprint "easyedapro:C0603")
      (fields
        (field (name "Manufacturer Part") "CL10A105KB8NNNC")
        (field (name "Manufacturer") "SAMSUNG(三星)")
      )
      (libsource (lib "easyedapro") (part "CL10A105KB8NNNC"))
    )
    (comp (ref "C42") (value "100nF") (libsource (lib "easyedapro") (part "CL05B104KO5NNNC")))
    (comp (ref "C43") (value "100nF") (libsource (lib "easyedapro") (part "CL05B104KO5NNNC")))
    (comp (ref "C44") (value "100nF") (libsource (lib "easyedapro") (part "CL05B104KO5NNNC")))
    (comp (ref "C46") (value "100nF") (libsource (lib "easyedapro") (part "CL05B104KO5NNNC")))
    (comp (ref "C47") (value "100nF") (libsource (lib "easyedapro") (part "CL05B104KO5NNNC")))
    (comp (ref "C48")
      (value "100nF")
      (footprint "easyedapro:C0402")
      (fields
        (field (name "Manufacturer Part") "CL05B104KO5NNNC")
        (field (name "Manufacturer") "SAMSUNG(三星)")
      )
      (libsource (lib "") (part "CL05B104KO5NNNC_1"))
    )
    (comp (ref "C49")
      (value "1uF")
      (fields
        (field (name "Manufacturer Part") "CL05A105KA5NQNC")
        (field (name "Manufacturer") "SAMSUNG(三星)")
      )
      (libsource (lib "easyedapro") (part "CL05A105KA5NQNC"))
    )
    (comp (ref "C50") (value "100nF") (libsource (lib "easyedapro") (part "CL05B104KO5NNNC")))
    (comp (ref "C51") (value "100nF") (libsource (lib "easyedapro") (part "CL05B104KO5NNNC")))
    (comp (ref "C52")
      (value "2.2nF")
      (footprint "easyedapro:CAP-SMD_L7.8-W5.4-P9.60_TMY1222M")
      (fields (field (name "Manufacturer Part") "TMY1222M") (field (name "Manufacturer") "TRX(特锐祥)"))
      (libsource (lib "easyedapro") (part "TMY1222M"))
    )
    (comp (ref "CN1")
      (value "SM06B-GHS-TB(LF)(SN)")
      (footprint "easyedapro:CONN-TH_SM06B-GHS-TB-LF-SN")
      (fields (field (name "Manufacturer") "JST"))
      (libsource (lib "easyedapro") (part "SM06B-GHS-TB(LF)(SN)"))
    )
    (comp (ref "CN4")
      (value "SM06B-GHS-TB(LF)(SN)")
      (footprint "easyedapro:CONN-TH_SM06B-GHS-TB-LF-SN")
      (fields (field (name "Manufacturer") "JST"))
      (libsource (lib "easyedapro") (part "SM06B-GHS-TB(LF)(SN)"))
    )
    (comp (ref "CN5")
      (value "SM06B-GHS-TB(LF)(SN)")
      (footprint "easyedapro:CONN-TH_SM06B-GHS-TB-LF-SN")
      (fields (field (name "Manufacturer") "JST"))
      (libsource (lib "easyedapro") (part "SM06B-GHS-TB(LF)(SN)"))
    )
    (comp (ref "D1")
      (value "ESDCAN03-2BWY")
      (footprint "easyedapro:SOT-323-3_L2.0-W1.3-P1.30-LS2.1-BR")
      (fields (field (name "Manufacturer") "ST(意法半导体)"))
      (libsource (lib "easyedapro") (part "ESDCAN03-2BWY"))
    )
    (comp (ref "D10") (value "H5VL10B") (libsource (lib "easyedapro") (part "H5VL10B")))
    (comp (ref "D11") (value "H5VL10B") (libsource (lib "easyedapro") (part "H5VL10B")))
    (comp (ref "D12")
      (value "H5VU25U")
      (fields (field (name "Manufacturer") "宏迦橙"))
      (libsource (lib "easyedapro") (part "H5VU25U"))
    )
    (comp (ref "D16") (value "H5VL10B") (libsource (lib "easyedapro") (part "H5VL10B")))
    (comp (ref "D17")
      (value "H5VU25U")
      (fields (field (name "Manufacturer") "宏迦橙"))
      (libsource (lib "easyedapro") (part "H5VU25U"))
    )
    (comp (ref "L1")
      (value "ACT1210-510-2P-TL00")
      (footprint "easyedapro:FILTER-SMD_4P-L3.2-W2.5-BL_ACT1210")
      (fields (field (name "Manufacturer") "TDK"))
      (libsource (lib "easyedapro") (part "ACT1210-510-2P-TL00"))
    )
    (comp (ref "L2")
      (value "GZ1608D601TF")
      (footprint "easyedapro:L0603")
      (fields (field (name "Manufacturer") "Sunlord(顺络)"))
      (libsource (lib "easyedapro") (part "GZ1608D601TF"))
    )
    (comp (ref "Q1")
      (value "AO3400A")
      (fields (field (name "Manufacturer") "AOS"))
      (libsource (lib "easyedapro") (part "AO3400A"))
    )
    (comp (ref "R5")
      (value "33Ω")
      (footprint "easyedapro:R0402")
      (fields
        (field (name "Manufacturer Part") "0402WGF330JTCE")
        (field (name "Manufacturer") "UNI-ROYAL(厚声)")
      )
      (libsource (lib "easyedapro") (part "0402WGF330JTCE"))
    )
    (comp (ref "R16")
      (value "10kΩ")
      (fields
        (field (name "Manufacturer Part") "0402WGF1002TCE")
        (field (name "Manufacturer") "UNI-ROYAL(厚声)")
      )
      (libsource (lib "easyedapro") (part "0402WGF1002TCE"))
    )
    (comp (ref "R26")
      (value "33Ω")
      (footprint "easyedapro:R0402")
      (fields
        (field (name "Manufacturer Part") "0402WGF330JTCE")
        (field (name "Manufacturer") "UNI-ROYAL(厚声)")
      )
      (libsource (lib "easyedapro") (part "0402WGF330JTCE"))
    )
    (comp (ref "R28")
      (value "100kΩ")
      (footprint "easyedapro:R0402")
      (fields
        (field (name "Manufacturer Part") "0402WGF1003TCE")
        (field (name "Manufacturer") "UNI-ROYAL(厚声)")
      )
      (libsource (lib "easyedapro") (part "0402WGF1003TCE"))
    )
    (comp (ref "R32")
      (value "100kΩ")
      (footprint "easyedapro:R0402")
      (fields
        (field (name "Manufacturer Part") "0402WGF1003TCE")
        (field (name "Manufacturer") "UNI-ROYAL(厚声)")
      )
      (libsource (lib "easyedapro") (part "0402WGF1003TCE"))
    )
    (comp (ref "R33")
      (value "100kΩ")
      (footprint "easyedapro:R0402")
      (fields
        (field (name "Manufacturer Part") "0402WGF1003TCE")
        (field (name "Manufacturer") "UNI-ROYAL(厚声)")
      )
      (libsource (lib "easyedapro") (part "0402WGF1003TCE"))
    )
    (comp (ref "R34")
      (value "100kΩ")
      (footprint "easyedapro:R0402")
      (fields
        (field (name "Manufacturer Part") "0402WGF1003TCE")
        (field (name "Manufacturer") "UNI-ROYAL(厚声)")
      )
      (libsource (lib "easyedapro") (part "0402WGF1003TCE"))
    )
    (comp (ref "R35")
      (value "100kΩ")
      (footprint "easyedapro:R0402")
      (fields
        (field (name "Manufacturer Part") "0402WGF1003TCE")
        (field (name "Manufacturer") "UNI-ROYAL(厚声)")
      )
      (libsource (lib "easyedapro") (part "0402WGF1003TCE"))
    )
    (comp (ref "R36")
      (value "100kΩ")
      (footprint "easyedapro:R0402")
      (fields
        (field (name "Manufacturer Part") "0402WGF1003TCE")
        (field (name "Manufacturer") "UNI-ROYAL(厚声)")
      )
      (libsource (lib "easyedapro") (part "0402WGF1003TCE"))
    )
    (comp (ref "R37")
      (value "100kΩ")
      (footprint "easyedapro:R0402")
      (fields
        (field (name "Manufacturer Part") "0402WGF1003TCE")
        (field (name "Manufacturer") "UNI-ROYAL(厚声)")
      )
      (libsource (lib "easyedapro") (part "0402WGF1003TCE"))
    )
    (comp (ref "R39")
      (value "10kΩ")
      (footprint "easyedapro:R0402")
      (fields
        (field (name "Manufacturer Part") "0402WGF1002TCE")
        (field (name "Manufacturer") "UNI-ROYAL(厚声)")
      )
      (libsource (lib "easyedapro") (part "10kΩ"))
    )
    (comp (ref "R40")
      (value "4.7kΩ")
      (footprint "easyedapro:R0402")
      (fields
        (field (name "Manufacturer Part") "0402WGF4701TCE")
        (field (name "Manufacturer") "UNI-ROYAL(厚声)")
      )
      (libsource (lib "easyedapro") (part "0402WGF4701TCE"))
    )
    (comp (ref "R41")
      (value "47kΩ")
      (footprint "easyedapro:R0402")
      (fields
        (field (name "Manufacturer Part") "0402WGF4702TCE")
        (field (name "Manufacturer") "UNI-ROYAL(厚声)")
      )
      (libsource (lib "easyedapro") (part "0402WGF4702TCE"))
    )
    (comp (ref "R45") (value "10kΩ") (libsource (lib "easyedapro") (part "0402WGF1002TCE")))
    (comp (ref "R46")
      (value "10kΩ")
      (footprint "easyedapro:R0402")
      (fields
        (field (name "Manufacturer Part") "0402WGF1002TCE")
        (field (name "Manufacturer") "UNI-ROYAL(厚声)")
      )
      (libsource (lib "easyedapro") (part "10kΩ"))
    )
    (comp (ref "RN4")
      (value "33Ω")
      (footprint "easyedapro:RES-ARRAY-SMD_0402-8P-L2.0-W1.0-BL")
      (fields (field (name "Manufacturer Part") "YC124-FR-0733RL") (field (name "Manufacturer") "YAGEO(国巨)"))
      (libsource (lib "easyedapro") (part "YC124-FR-0733RL"))
    )
    (comp (ref "RN5")
      (value "33Ω")
      (footprint "easyedapro:RES-ARRAY-SMD_0402-8P-L2.0-W1.0-BL")
      (fields (field (name "Manufacturer Part") "YC124-FR-0733RL") (field (name "Manufacturer") "YAGEO(国巨)"))
      (libsource (lib "easyedapro") (part "YC124-FR-0733RL"))
    )
    (comp (ref "RN6")
      (value "33Ω")
      (footprint "easyedapro:RES-ARRAY-SMD_0402-8P-L2.0-W1.0-BL")
      (fields (field (name "Manufacturer Part") "YC124-FR-0733RL") (field (name "Manufacturer") "YAGEO(国巨)"))
      (libsource (lib "easyedapro") (part "YC124-FR-0733RL"))
    )
    (comp (ref "RN7")
      (value "33Ω")
      (footprint "easyedapro:RES-ARRAY-SMD_0402-8P-L2.0-W1.0-BL")
      (fields (field (name "Manufacturer Part") "YC124-FR-0733RL") (field (name "Manufacturer") "YAGEO(国巨)"))
      (libsource (lib "easyedapro") (part "YC124-FR-0733RL"))
    )
    (comp (ref "RN8")
      (value "33Ω")
      (footprint "easyedapro:RES-ARRAY-SMD_0402-8P-L2.0-W1.0-BL")
      (fields (field (name "Manufacturer Part") "YC124-FR-0733RL") (field (name "Manufacturer") "YAGEO(国巨)"))
      (libsource (lib "easyedapro") (part "YC124-FR-0733RL"))
    )
    (comp (ref "TP1")
      (value "~")
      (footprint "easyedapro:TEST PAD")
      (libsource (lib "easyedapro") (part "TEST PAD"))
    )
    (comp (ref "TP3")
      (value "~")
      (footprint "easyedapro:TEST PAD")
      (libsource (lib "easyedapro") (part "TEST PAD"))
    )
    (comp (ref "TP4")
      (value "~")
      (footprint "easyedapro:TEST PAD")
      (libsource (lib "easyedapro") (part "TEST PAD"))
    )
    (comp (ref "TP10")
      (value "~")
      (footprint "easyedapro:TEST PAD")
      (libsource (lib "easyedapro") (part "TEST PAD"))
    )
    (comp (ref "U3")
      (value "CA-IS2062VW")
      (footprint "easyedapro:CA-IS305XW")
      (fields (field (name "Manufacturer") "Chipanalog(川土微)"))
      (libsource (lib "easyedapro") (part "CA-IS2062VW"))
    )
    (comp (ref "U13")
      (value "SN74AVC4T774PWR")
      (fields (field (name "Manufacturer") "TI(德州仪器)"))
      (libsource (lib "easyedapro") (part "SN74AVC4T774PWR"))
    )
    (comp (ref "U15")
      (value "SN74AVC4T774PWR")
      (fields (field (name "Manufacturer") "TI(德州仪器)"))
      (libsource (lib "easyedapro") (part "SN74AVC4T774PWR"))
    )
    (comp (ref "U16")
      (value "TPS22929DDBVR")
      (footprint "easyedapro:SOT-23-6_L2.9-W1.6-P0.95-LS2.8-BL")
      (fields (field (name "Manufacturer") "TI(德州仪器)"))
      (libsource (lib "easyedapro") (part "TPS22929DDBVR"))
    )
  )
  (nets
    (net (code "1") (name "3.3V") (class "Default")
      (node (ref "C11") (pin "2") (pinfunction "2_2") (pintype "unspecified"))
      (node (ref "C12") (pin "2") (pinfunction "2_2") (pintype "unspecified"))
      (node (ref "C13") (pin "2") (pinfunction "2_2") (pintype "input"))
      (node (ref "C16") (pin "2") (pinfunction "2_2") (pintype "unspecified"))
      (node (ref "C17") (pin "2") (pinfunction "2_2") (pintype "input"))
      (node (ref "C22") (pin "1") (pinfunction "1_1") (pintype "unspecified"))
      (node (ref "C23") (pin "2") (pinfunction "2_2") (pintype "input"))
      (node (ref "C24") (pin "1") (pinfunction "1_1") (pintype "input"))
      (node (ref "C26") (pin "2") (pinfunction "2_2") (pintype "unspecified"))
      (node (ref "C29") (pin "2") (pinfunction "2_2") (pintype "input"))
      (node (ref "C31") (pin "2") (pinfunction "2_2") (pintype "input"))
      (node (ref "C32") (pin "2") (pinfunction "2_2") (pintype "input"))
      (node (ref "C37") (pin "2") (pinfunction "2_2") (pintype "input"))
      (node (ref "C43") (pin "1") (pinfunction "1_1") (pintype "unspecified"))
      (node (ref "C45") (pin "2") (pinfunction "2_2") (pintype "unspecified"))
      (node (ref "C47") (pin "1") (pinfunction "1_1") (pintype "unspecified"))
      (node (ref "C6") (pin "2") (pinfunction "2_2") (pintype "unspecified"))
      (node (ref "C9") (pin "2") (pinfunction "2_2") (pintype "input"))
      (node (ref "CN2") (pin "2") (pinfunction "2_2") (pintype "unspecified"))
      (node (ref "CN3") (pin "1") (pinfunction "1_1") (pintype "unspecified"))
      (node (ref "FPC1") (pin "9") (pinfunction "9_9") (pintype "input"))
      (node (ref "L3") (pin "2") (pinfunction "2_2") (pintype "unspecified"))
      (node (ref "L5") (pin "1") (pinfunction "1_1") (pintype "input"))
      (node (ref "LED1") (pin "2") (pinfunction "A_2") (pintype "input"))
      (node (ref "R10") (pin "2") (pinfunction "2_2") (pintype "input"))
      (node (ref "R11") (pin "2") (pinfunction "2_2") (pintype "input"))
      (node (ref "R12") (pin "2") (pinfunction "2_2") (pintype "input"))
      (node (ref "R15") (pin "1") (pinfunction "1_1") (pintype "input"))
      (node (ref "R16") (pin "2") (pinfunction "2_2") (pintype "input"))
      (node (ref "R17") (pin "1") (pinfunction "1_1") (pintype "input"))
      (node (ref "R18") (pin "1") (pinfunction "1_1") (pintype "input"))
      (node (ref "R20") (pin "1") (pinfunction "1_1") (pintype "input"))
      (node (ref "R21") (pin "1") (pinfunction "1_1") (pintype "input"))
      (node (ref "R3") (pin "2") (pinfunction "2_2") (pintype "input"))
      (node (ref "R42") (pin "2") (pinfunction "2_2") (pintype "input"))
      (node (ref "R43") (pin "2") (pinfunction "2_2") (pintype "input"))
      (node (ref "R44") (pin "2") (pinfunction "2_2") (pintype "input"))
      (node (ref "R45") (pin "2") (pinfunction "2_2") (pintype "input"))
      (node (ref "R6") (pin "2") (pinfunction "2_2") (pintype "input"))
      (node (ref "R7") (pin "2") (pinfunction "2_2") (pintype "input"))
      (node (ref "R8") (pin "2") (pinfunction "2_2") (pintype "input"))
      (node (ref "R9") (pin "1") (pinfunction "1_1") (pintype "input"))
      (node (ref "SW1") (pin "3") (pinfunction "3_3") (pintype "input"))
      (node (ref "TP6") (pin "1") (pinfunction "TEST_PAD1_1") (pintype "input"))
      (node (ref "U12") (pin "1") (pinfunction "VDD_1") (pintype "unspecified"))
      (node (ref "U12") (pin "36") (pinfunction "VDD_36") (pintype "unspecified"))
      (node (ref "U12") (pin "64") (pinfunction "VDD_64") (pintype "unspecified"))
      (node (ref "U13") (pin "16") (pinfunction "VCCA_16") (pintype "unspecified"))
      (node (ref "U14") (pin "14") (pinfunction "VCC_14") (pintype "unspecified"))
      (node (ref "U15") (pin "16") (pinfunction "VCCA_16") (pintype "unspecified"))
      (node (ref "U15") (pin "8") (pinfunction "DIR4_8") (pintype "unspecified"))
      (node (ref "U16") (pin "4") (pinfunction "VIN_4") (pintype "input"))
      (node (ref "U16") (pin "6") (pinfunction "VIN_6") (pintype "input"))
      (node (ref "U2") (pin "4") (pinfunction "VIN_4") (pintype "input"))
      (node (ref "U2") (pin "6") (pinfunction "VIN_6") (pintype "input"))
      (node (ref "U3") (pin "7") (pinfunction "VCCL_7") (pintype "unspecified"))
      (node (ref "U5") (pin "2") (pinfunction "VDD_2") (pintype "unspecified"))
      (node (ref "U6") (pin "3") (pinfunction "IO2_3") (pintype "unspecified"))
      (node (ref "U6") (pin "7") (pinfunction "IO3_7") (pintype "unspecified"))
      (node (ref "U6") (pin "8") (pinfunction "VCC_8") (pintype "unspecified"))
      (node (ref "U7") (pin "4") (pinfunction "EN_4") (pintype "unspecified"))
      (node (ref "U8") (pin "8") (pinfunction "VCC_8") (pintype "input"))
      (node (ref "U9") (pin "4") (pinfunction "VCC_4") (pintype "unspecified"))
    )
    (net (code "2") (name "3.3V_ANA") (class "Default")
      (node (ref "C34") (pin "2") (pinfunction "2_2") (pintype "unspecified"))
      (node (ref "C36") (pin "2") (pinfunction "2_2") (pintype "input"))
      (node (ref "L5") (pin "2") (pinfunction "2_2") (pintype "input"))
      (node (ref "U12") (pin "13") (pinfunction "VDDA_13") (pintype "unspecified"))
    )
    (net (code "3") (name "5V") (class "Default")
      (node (ref "C10") (pin "2") (pinfunction "2_2") (pintype "input"))
      (node (ref "C20") (pin "2") (pinfunction "2_2") (pintype "input"))
      (node (ref "C7") (pin "2") (pinfunction "2_2") (pintype "unspecified"))
      (node (ref "C8") (pin "2") (pinfunction "2_2") (pintype "input"))
      (node (ref "L4") (pin "1") (pinfunction "1_1") (pintype "unspecified"))
      (node (ref "TP9") (pin "1") (pinfunction "TEST_PAD1_1") (pintype "input"))
      (node (ref "U10") (pin "1") (pinfunction "VOUT_1") (pintype "input"))
      (node (ref "U3") (pin "1") (pinfunction "VCC_1") (pintype "unspecified"))
      (node (ref "U4") (pin "1") (pinfunction "EN_1") (pintype "input"))
      (node (ref "U4") (pin "4") (pinfunction "VIN_4") (pintype "input"))
      (node (ref "U7") (pin "3") (pinfunction "FB_3") (pintype "unspecified"))
      (node (ref "U7") (pin "6") (pinfunction "VIN_6") (pintype "unspecified"))
    )
    (net (code "4") (name "12V") (class "Default")
      (node (ref "C15") (pin "2") (pinfunction "2_2") (pintype "unspecified"))
      (node (ref "C18") (pin "2") (pinfunction "2_2") (pintype "unspecified"))
      (node (ref "C19") (pin "2") (pinfunction "2_2") (pintype "unspecified"))
      (node (ref "FPC1") (pin "11") (pinfunction "11_11") (pintype "input"))
      (node (ref "FPC1") (pin "2") (pinfunction "2_2") (pintype "input"))
      (node (ref "TP8") (pin "1") (pinfunction "TEST_PAD1_1") (pintype "input"))
      (node (ref "U7") (pin "5") (pinfunction "VOUT_5") (pintype "unspecified"))
    )
    (net (code "5") (name "ADC_VIO") (class "Default")
      (node (ref "C48") (pin "1") (pinfunction "1_1") (pintype "input"))
      (node (ref "D10") (pin "2") (pinfunction "A_2") (pintype "unspecified"))
      (node (ref "R39") (pin "2") (pinfunction "2_2") (pintype "input"))
      (node (ref "R40") (pin "1") (pinfunction "1_1") (pintype "input"))
      (node (ref "U12") (pin "11") (pinfunction "PC3_11") (pintype "unspecified"))
    )
    (net (code "6") (name "AUX_RXD") (class "Default")
      (node (ref "RN6") (pin "6") (pinfunction "6_6") (pintype "input"))
      (node (ref "U12") (pin "25") (pinfunction "PC5_25") (pintype "unspecified"))
    )
    (net (code "7") (name "AUX_SWO") (class "Default")
      (node (ref "RN6") (pin "7") (pinfunction "7_7") (pintype "input"))
      (node (ref "U12") (pin "47") (pinfunction "PF6_47") (pintype "unspecified"))
    )
    (net (code "8") (name "AUX_TXD") (class "Default")
      (node (ref "RN6") (pin "5") (pinfunction "5_5") (pintype "input"))
      (node (ref "U12") (pin "24") (pinfunction "PC4_24") (pintype "unspecified"))
    )
    (net (code "9") (name "BOOT0") (class "Default")
      (node (ref "D6") (pin "2") (pinfunction "A_2") (pintype "input"))
      (node (ref "R23") (pin "1") (pinfunction "1_1") (pintype "input"))
      (node (ref "SW1") (pin "4") (pinfunction "4_4") (pintype "input"))
      (node (ref "U12") (pin "60") (pinfunction "PF11/BOOT0_60") (pintype "unspecified"))
    )
    (net (code "10") (name "CAN_5V_IN") (class "Default")
      (node (ref "C3") (pin "2") (pinfunction "2_2") (pintype "unspecified"))
      (node (ref "L2") (pin "2") (pinfunction "2_2") (pintype "unspecified"))
      (node (ref "TP4") (pin "1") (pinfunction "TEST_PAD1_1") (pintype "input"))
      (node (ref "U3") (pin "11") (pinfunction "VISO_11") (pintype "unspecified"))
    )
    (net (code "11") (name "CAN_5V_OUT") (class "Default")
      (node (ref "C1") (pin "2") (pinfunction "2_2") (pintype "unspecified"))
      (node (ref "C2") (pin "2") (pinfunction "2_2") (pintype "input"))
      (node (ref "L2") (pin "1") (pinfunction "1_1") (pintype "unspecified"))
      (node (ref "U3") (pin "16") (pinfunction "VISO_16") (pintype "unspecified"))
    )
    (net (code "12") (name "CAN_GND") (class "Default")
      (node (ref "C1") (pin "1") (pinfunction "1_1") (pintype "unspecified"))
      (node (ref "C2") (pin "1") (pinfunction "1_1") (pintype "input"))
      (node (ref "C3") (pin "1") (pinfunction "1_1") (pintype "unspecified"))
      (node (ref "C52") (pin "2") (pinfunction "2_2") (pintype "unspecified"))
      (node (ref "CN1") (pin "1") (pinfunction "1_1") (pintype "unspecified"))
      (node (ref "CN1") (pin "6") (pinfunction "6_6") (pintype "unspecified"))
      (node (ref "CN1") (pin "7") (pinfunction "7_7") (pintype "unspecified"))
      (node (ref "CN1") (pin "8") (pinfunction "8_8") (pintype "unspecified"))
      (node (ref "D1") (pin "3") (pinfunction "K_3") (pintype "unspecified"))
      (node (ref "M1") (pin "1") (pinfunction "1_1") (pintype "input"))
      (node (ref "TP3") (pin "1") (pinfunction "TEST_PAD1_1") (pintype "input"))
      (node (ref "U3") (pin "10") (pinfunction "GND2_10") (pintype "unspecified"))
      (node (ref "U3") (pin "15") (pinfunction "GND2_15") (pintype "unspecified"))
      (node (ref "U3") (pin "9") (pinfunction "GND2_9") (pintype "unspecified"))
    )
    (net (code "13") (name "CAN_HI") (class "Default")
      (node (ref "CN1") (pin "3") (pinfunction "3_3") (pintype "unspecified"))
      (node (ref "CN1") (pin "5") (pinfunction "5_5") (pintype "unspecified"))
      (node (ref "D1") (pin "2") (pinfunction "A_2") (pintype "unspecified"))
      (node (ref "L1") (pin "4") (pinfunction "4_4") (pintype "unspecified"))
    )
    (net (code "14") (name "CAN_LO") (class "Default")
      (node (ref "CN1") (pin "2") (pinfunction "2_2") (pintype "unspecified"))
      (node (ref "CN1") (pin "4") (pinfunction "4_4") (pintype "unspecified"))
      (node (ref "D1") (pin "1") (pinfunction "A_1") (pintype "unspecified"))
      (node (ref "L1") (pin "3") (pinfunction "3_3") (pintype "unspecified"))
    )
    (net (code "15") (name "CAN_RX") (class "Default")
      (node (ref "R5") (pin "1") (pinfunction "1_1") (pintype "input"))
      (node (ref "U12") (pin "61") (pinfunction "PB8_61") (pintype "unspecified"))
    )
    (net (code "16") (name "CAN_TX") (class "Default")
      (node (ref "R16") (pin "1") (pinfunction "1_1") (pintype "input"))
      (node (ref "R19") (pin "2") (pinfunction "2_2") (pintype "input"))
      (node (ref "U3") (pin "3") (pinfunction "TXD_3") (pintype "unspecified"))
    )
    (net (code "17") (name "CONSOLE_RXD") (class "Default")
      (node (ref "CN3") (pin "3") (pinfunction "3_3") (pintype "unspecified"))
      (node (ref "D9") (pin "4") (pinfunction "4_4") (pintype "unspecified"))
      (node (ref "D9") (pin "7") (pinfunction "7_7") (pintype "unspecified"))
      (node (ref "U12") (pin "38") (pinfunction "PC7_38") (pintype "unspecified"))
    )
    (net (code "18") (name "CONSOLE_TXD") (class "Default")
      (node (ref "CN3") (pin "2") (pinfunction "2_2") (pintype "unspecified"))
      (node (ref "D9") (pin "5") (pinfunction "5_5") (pintype "unspecified"))
      (node (ref "D9") (pin "6") (pinfunction "6_6") (pintype "unspecified"))
      (node (ref "U12") (pin "37") (pinfunction "PC6_37") (pintype "unspecified"))
    )
    (net (code "19") (name "DISP_CS") (class "Default")
      (node (ref "FPC1") (pin "7") (pinfunction "7_7") (pintype "input"))
      (node (ref "U12") (pin "54") (pinfunction "PD2_54") (pintype "unspecified"))
    )
    (net (code "20") (name "DISP_DC") (class "Default")
      (node (ref "FPC1") (pin "5") (pinfunction "5_5") (pintype "input"))
      (node (ref "U12") (pin "48") (pinfunction "PF7_48") (pintype "unspecified"))
    )
    (net (code "21") (name "DISP_RST") (class "Default")
      (node (ref "FPC1") (pin "6") (pinfunction "6_6") (pintype "input"))
      (node (ref "U12") (pin "53") (pinfunction "PC12_53") (pintype "unspecified"))
    )
    (net (code "22") (name "FLASH_CS") (class "Default")
      (node (ref "R9") (pin "2") (pinfunction "2_2") (pintype "input"))
      (node (ref "RN3") (pin "8") (pinfunction "8_8") (pintype "input"))
      (node (ref "U6") (pin "1") (pinfunction "CS#_1") (pintype "unspecified"))
    )
    (net (code "23") (name "GND") (class "Default")
      (node (ref "BT1") (pin "3") (pinfunction "-_3") (pintype "input"))
      (node (ref "C10") (pin "1") (pinfunction "1_1") (pintype "input"))
      (node (ref "C11") (pin "1") (pinfunction "1_1") (pintype "unspecified"))
      (node (ref "C12") (pin "1") (pinfunction "1_1") (pintype "unspecified"))
      (node (ref "C13") (pin "1") (pinfunction "1_1") (pintype "input"))
      (node (ref "C14") (pin "1") (pinfunction "1_1") (pintype "unspecified"))
      (node (ref "C15") (pin "1") (pinfunction "1_1") (pintype "unspecified"))
      (node (ref "C16") (pin "1") (pinfunction "1_1") (pintype "unspecified"))
      (node (ref "C17") (pin "1") (pinfunction "1_1") (pintype "input"))
      (node (ref "C18") (pin "1") (pinfunction "1_1") (pintype "unspecified"))
      (node (ref "C19") (pin "1") (pinfunction "1_1") (pintype "unspecified"))
      (node (ref "C20") (pin "1") (pinfunction "1_1") (pintype "input"))
      (node (ref "C21") (pin "1") (pinfunction "1_1") (pintype "unspecified"))
      (node (ref "C22") (pin "2") (pinfunction "2_2") (pintype "unspecified"))
      (node (ref "C23") (pin "1") (pinfunction "1_1") (pintype "input"))
      (node (ref "C24") (pin "2") (pinfunction "2_2") (pintype "input"))
      (node (ref "C25") (pin "1") (pinfunction "1_1") (pintype "unspecified"))
      (node (ref "C26") (pin "1") (pinfunction "1_1") (pintype "unspecified"))
      (node (ref "C27") (pin "1") (pinfunction "1_1") (pintype "input"))
      (node (ref "C28") (pin "1") (pinfunction "1_1") (pintype "input"))
      (node (ref "C29") (pin "1") (pinfunction "1_1") (pintype "input"))
      (node (ref "C30") (pin "2") (pinfunction "2_2") (pintype "input"))
      (node (ref "C31") (pin "1") (pinfunction "1_1") (pintype "input"))
      (node (ref "C32") (pin "1") (pinfunction "1_1") (pintype "input"))
      (node (ref "C33") (pin "1") (pinfunction "1_1") (pintype "input"))
      (node (ref "C34") (pin "1") (pinfunction "1_1") (pintype "unspecified"))
      (node (ref "C35") (pin "1") (pinfunction "1_1") (pintype "input"))
      (node (ref "C36") (pin "1") (pinfunction "1_1") (pintype "input"))
      (node (ref "C37") (pin "1") (pinfunction "1_1") (pintype "input"))
      (node (ref "C38") (pin "1") (pinfunction "1_1") (pintype "input"))
      (node (ref "C39") (pin "2") (pinfunction "2_2") (pintype "unspecified"))
      (node (ref "C4") (pin "1") (pinfunction "1_1") (pintype "input"))
      (node (ref "C40") (pin "2") (pinfunction "2_2") (pintype "unspecified"))
      (node (ref "C41") (pin "2") (pinfunction "2_2") (pintype "unspecified"))
      (node (ref "C42") (pin "2") (pinfunction "2_2") (pintype "unspecified"))
      (node (ref "C43") (pin "2") (pinfunction "2_2") (pintype "unspecified"))
      (node (ref "C44") (pin "2") (pinfunction "2_2") (pintype "unspecified"))
      (node (ref "C45") (pin "1") (pinfunction "1_1") (pintype "unspecified"))
      (node (ref "C46") (pin "2") (pinfunction "2_2") (pintype "unspecified"))
      (node (ref "C47") (pin "2") (pinfunction "2_2") (pintype "unspecified"))
      (node (ref "C48") (pin "2") (pinfunction "2_2") (pintype "input"))
      (node (ref "C49") (pin "1") (pinfunction "1_1") (pintype "unspecified"))
      (node (ref "C5") (pin "2") (pinfunction "2_2") (pintype "input"))
      (node (ref "C50") (pin "2") (pinfunction "2_2") (pintype "unspecified"))
      (node (ref "C51") (pin "2") (pinfunction "2_2") (pintype "unspecified"))
      (node (ref "C52") (pin "1") (pinfunction "1_1") (pintype "unspecified"))
      (node (ref "C6") (pin "1") (pinfunction "1_1") (pintype "unspecified"))
      (node (ref "C7") (pin "1") (pinfunction "1_1") (pintype "unspecified"))
      (node (ref "C8") (pin "1") (pinfunction "1_1") (pintype "input"))
      (node (ref "CN2") (pin "1") (pinfunction "1_1") (pintype "unspecified"))
      (node (ref "CN2") (pin "7") (pinfunction "7_7") (pintype "unspecified"))
      (node (ref "CN2") (pin "8") (pinfunction "8_8") (pintype "unspecified"))
      (node (ref "CN3") (pin "6") (pinfunction "6_6") (pintype "unspecified"))
      (node (ref "CN3") (pin "7") (pinfunction "7_7") (pintype "unspecified"))
      (node (ref "CN3") (pin "8") (pinfunction "8_8") (pintype "unspecified"))
      (node (ref "CN4") (pin "6") (pinfunction "6_6") (pintype "unspecified"))
      (node (ref "CN4") (pin "7") (pinfunction "7_7") (pintype "unspecified"))
      (node (ref "CN4") (pin "8") (pinfunction "8_8") (pintype "unspecified"))
      (node (ref "CN5") (pin "6") (pinfunction "6_6") (pintype "unspecified"))
      (node (ref "CN5") (pin "7") (pinfunction "7_7") (pintype "unspecified"))
      (node (ref "CN5") (pin "8") (pinfunction "8_8") (pintype "unspecified"))
      (node (ref "D10") (pin "1") (pinfunction "C_1") (pintype "unspecified"))
      (node (ref "D11") (pin "1") (pinfunction "C_1") (pintype "unspecified"))
      (node (ref "D12") (pin "3") (pinfunction "3_3") (pintype "unspecified"))
      (node (ref "D12") (pin "8") (pinfunction "8_8") (pintype "unspecified"))
      (node (ref "D13") (pin "1") (pinfunction "C_1") (pintype "input"))
      (node (ref "D14") (pin "1") (pinfunction "C_1") (pintype "input"))
      (node (ref "D15") (pin "1") (pinfunction "C_1") (pintype "input"))
      (node (ref "D16") (pin "1") (pinfunction "C_1") (pintype "unspecified"))
      (node (ref "D17") (pin "3") (pinfunction "3_3") (pintype "unspecified"))
      (node (ref "D17") (pin "8") (pinfunction "8_8") (pintype "unspecified"))
      (node (ref "D2") (pin "2") (pinfunction "2_2") (pintype "unspecified"))
      (node (ref "D2") (pin "3") (pinfunction "3_3") (pintype "unspecified"))
      (node (ref "D2") (pin "4") (pinfunction "4_4") (pintype "unspecified"))
      (node (ref "D2") (pin "7") (pinfunction "7_7") (pintype "unspecified"))
      (node (ref "D2") (pin "8") (pinfunction "8_8") (pintype "unspecified"))
      (node (ref "D2") (pin "9") (pinfunction "9_9") (pintype "unspecified"))
      (node (ref "D3") (pin "2") (pinfunction "2_2") (pintype "unspecified"))
      (node (ref "D3") (pin "3") (pinfunction "3_3") (pintype "unspecified"))
      (node (ref "D3") (pin "8") (pinfunction "8_8") (pintype "unspecified"))
      (node (ref "D3") (pin "9") (pinfunction "9_9") (pintype "unspecified"))
      (node (ref "D4") (pin "3") (pinfunction "3_3") (pintype "unspecified"))
      (node (ref "D4") (pin "8") (pinfunction "8_8") (pintype "unspecified"))
      (node (ref "D5") (pin "2") (pinfunction "A_2") (pintype "unspecified"))
      (node (ref "D6") (pin "1") (pinfunction "C_1") (pintype "input"))
      (node (ref "D7") (pin "3") (pinfunction "3_3") (pintype "unspecified"))
      (node (ref "D7") (pin "4") (pinfunction "4_4") (pintype "unspecified"))
      (node (ref "D7") (pin "5") (pinfunction "5_5") (pintype "unspecified"))
      (node (ref "D7") (pin "6") (pinfunction "6_6") (pintype "unspecified"))
      (node (ref "D7") (pin "7") (pinfunction "7_7") (pintype "unspecified"))
      (node (ref "D7") (pin "8") (pinfunction "8_8") (pintype "unspecified"))
      (node (ref "D8") (pin "1") (pinfunction "C_1") (pintype "input"))
      (node (ref "D9") (pin "3") (pinfunction "3_3") (pintype "unspecified"))
      (node (ref "D9") (pin "8") (pinfunction "8_8") (pintype "unspecified"))
      (node (ref "FPC1") (pin "1") (pinfunction "1_1") (pintype "input"))
      (node (ref "FPC1") (pin "12") (pinfunction "12_12") (pintype "input"))
      (node (ref "FPC1") (pin "13") (pinfunction "13_13") (pintype "input"))
      (node (ref "FPC1") (pin "14") (pinfunction "14_14") (pintype "input"))
      (node (ref "M2") (pin "1") (pinfunction "1_1") (pintype "input"))
      (node (ref "M3") (pin "1") (pinfunction "1_1") (pintype "input"))
      (node (ref "M4") (pin "1") (pinfunction "1_1") (pintype "input"))
      (node (ref "Q1") (pin "2") (pinfunction "S_2") (pintype "unspecified"))
      (node (ref "R14") (pin "1") (pinfunction "1_1") (pintype "input"))
      (node (ref "R2") (pin "1") (pinfunction "1_1") (pintype "input"))
      (node (ref "R22") (pin "2") (pinfunction "2_2") (pintype "input"))
      (node (ref "R23") (pin "2") (pinfunction "2_2") (pintype "input"))
      (node (ref "R24") (pin "2") (pinfunction "2_2") (pintype "input"))
      (node (ref "R25") (pin "1") (pinfunction "1_1") (pintype "input"))
      (node (ref "R27") (pin "1") (pinfunction "1_1") (pintype "input"))
      (node (ref "R37") (pin "1") (pinfunction "1_1") (pintype "input"))
      (node (ref "R39") (pin "1") (pinfunction "1_1") (pintype "input"))
      (node (ref "R4") (pin "1") (pinfunction "1_1") (pintype "input"))
      (node (ref "R41") (pin "1") (pinfunction "1_1") (pintype "input"))
      (node (ref "RN2") (pin "1") (pinfunction "1_1") (pintype "input"))
      (node (ref "RN2") (pin "8") (pinfunction "8_8") (pintype "input"))
      (node (ref "SW2") (pin "3") (pinfunction "3_3") (pintype "input"))
      (node (ref "SW3") (pin "4") (pinfunction "4_4") (pintype "unspecified"))
      (node (ref "SW3") (pin "5") (pinfunction "5_5") (pintype "unspecified"))
      (node (ref "SW3") (pin "6") (pinfunction "6_6") (pintype "unspecified"))
      (node (ref "SW3") (pin "7") (pinfunction "7_7") (pintype "unspecified"))
      (node (ref "SW3") (pin "C") (pinfunction "C_C") (pintype "unspecified"))
      (node (ref "TP2") (pin "1") (pinfunction "TEST_PAD1_1") (pintype "input"))
      (node (ref "U1") (pin "10") (pinfunction "10_10") (pintype "unspecified"))
      (node (ref "U1") (pin "11") (pinfunction "11_11") (pintype "unspecified"))
      (node (ref "U1") (pin "12") (pinfunction "12_12") (pintype "unspecified"))
      (node (ref "U1") (pin "13") (pinfunction "13_13") (pintype "unspecified"))
      (node (ref "U1") (pin "6") (pinfunction "VSS_6") (pintype "unspecified"))
      (node (ref "U10") (pin "2") (pinfunction "GND_2") (pintype "input"))
      (node (ref "U10") (pin "5") (pinfunction "GND_5") (pintype "input"))
      (node (ref "U12") (pin "12") (pinfunction "VSSA_12") (pintype "unspecified"))
      (node (ref "U12") (pin "31") (pinfunction "VSS_31") (pintype "unspecified"))
      (node (ref "U12") (pin "63") (pinfunction "VSS_63") (pintype "unspecified"))
      (node (ref "U13") (pin "10") (pinfunction "GND_10") (pintype "unspecified"))
      (node (ref "U14") (pin "7") (pinfunction "GND_7") (pintype "unspecified"))
      (node (ref "U15") (pin "1") (pinfunction "DIR1_1") (pintype "unspecified"))
      (node (ref "U15") (pin "10") (pinfunction "GND_10") (pintype "unspecified"))
      (node (ref "U15") (pin "2") (pinfunction "DIR2_2") (pintype "unspecified"))
      (node (ref "U15") (pin "7") (pinfunction "DIR3_7") (pintype "unspecified"))
      (node (ref "U16") (pin "2") (pinfunction "GND_2") (pintype "input"))
      (node (ref "U16") (pin "5") (pinfunction "GND_5") (pintype "input"))
      (node (ref "U2") (pin "2") (pinfunction "GND_2") (pintype "input"))
      (node (ref "U2") (pin "5") (pinfunction "GND_5") (pintype "input"))
      (node (ref "U3") (pin "2") (pinfunction "GND1_2") (pintype "unspecified"))
      (node (ref "U3") (pin "8") (pinfunction "GND1_8") (pintype "unspecified"))
      (node (ref "U4") (pin "2") (pinfunction "GND_2") (pintype "input"))
      (node (ref "U5") (pin "5") (pinfunction "GND_5") (pintype "unspecified"))
      (node (ref "U6") (pin "4") (pinfunction "GND_4") (pintype "unspecified"))
      (node (ref "U7") (pin "2") (pinfunction "GND_2") (pintype "unspecified"))
      (node (ref "U8") (pin "4") (pinfunction "GND_4") (pintype "input"))
      (node (ref "U9") (pin "2") (pinfunction "GND_2") (pintype "unspecified"))
      (node (ref "U9") (pin "5") (pinfunction "WP_5") (pintype "unspecified"))
      (node (ref "USBC1") (pin "A1") (pinfunction "GND_A1") (pintype "input"))
      (node (ref "USBC1") (pin "A12") (pinfunction "GND_A12") (pintype "input"))
      (node (ref "USBC1") (pin "B1") (pinfunction "GND_B1") (pintype "input"))
      (node (ref "USBC1") (pin "B12") (pinfunction "GND_B12") (pintype "input"))
      (node (ref "X2") (pin "2") (pinfunction "GND_2") (pintype "input"))
      (node (ref "X2") (pin "4") (pinfunction "GND_4") (pintype "input"))
    )
    (net (code "24") (name "HS_DM") (class "Default")
      (node (ref "D7") (pin "2") (pinfunction "2_2") (pintype "unspecified"))
      (node (ref "D7") (pin "9") (pinfunction "9_9") (pintype "unspecified"))
      (node (ref "U12") (pin "34") (pinfunction "OTGHS1_D-_34") (pintype "unspecified"))
      (node (ref "USBC1") (pin "A7") (pinfunction "DN1_A7") (pintype "input"))
      (node (ref "USBC1") (pin "B7") (pinfunction "DN2_B7") (pintype "input"))
    )
    (net (code "25") (name "HS_DP") (class "Default")
      (node (ref "D7") (pin "1") (pinfunction "1_1") (pintype "unspecified"))
      (node (ref "D7") (pin "10") (pinfunction "10_10") (pintype "unspecified"))
      (node (ref "U12") (pin "35") (pinfunction "OTGHS1_D+_35") (pintype "unspecified"))
      (node (ref "USBC1") (pin "A6") (pinfunction "DP1_A6") (pintype "input"))
      (node (ref "USBC1") (pin "B6") (pinfunction "DP2_B6") (pintype "input"))
    )
    (net (code "26") (name "HS_R") (class "Default")
      (node (ref "R24") (pin "1") (pinfunction "1_1") (pintype "input"))
      (node (ref "U12") (pin "33") (pinfunction "OTGHS1_R_33") (pintype "unspecified"))
    )
    (net (code "27") (name "HS_VBUS") (class "Default")
      (node (ref "D5") (pin "1") (pinfunction "K_1") (pintype "unspecified"))
      (node (ref "U11") (pin "1") (pinfunction "1_1") (pintype "unspecified"))
      (node (ref "USBC1") (pin "A4") (pinfunction "VBUS_A4") (pintype "input"))
      (node (ref "USBC1") (pin "A9") (pinfunction "VBUS_A9") (pintype "input"))
      (node (ref "USBC1") (pin "B4") (pinfunction "VBUS_B4") (pintype "input"))
      (node (ref "USBC1") (pin "B9") (pinfunction "VBUS_B9") (pintype "input"))
    )
    (net (code "28") (name "I2C1_SCL") (class "Default")
      (node (ref "CN2") (pin "4") (pinfunction "4_4") (pintype "unspecified"))
      (node (ref "D4") (pin "2") (pinfunction "2_2") (pintype "unspecified"))
      (node (ref "D4") (pin "9") (pinfunction "9_9") (pintype "unspecified"))
      (node (ref "R15") (pin "2") (pinfunction "2_2") (pintype "input"))
      (node (ref "RN1") (pin "1") (pinfunction "1_1") (pintype "input"))
      (node (ref "RN1") (pin "8") (pinfunction "8_8") (pintype "input"))
      (node (ref "U12") (pin "58") (pinfunction "PB6_58") (pintype "unspecified"))
      (node (ref "U5") (pin "8") (pinfunction "SCL_8") (pintype "unspecified"))
      (node (ref "U9") (pin "1") (pinfunction "SCL_1") (pintype "unspecified"))
    )
    (net (code "29") (name "I2C1_SDA") (class "Default")
      (node (ref "CN2") (pin "3") (pinfunction "3_3") (pintype "unspecified"))
      (node (ref "D4") (pin "1") (pinfunction "1_1") (pintype "unspecified"))
      (node (ref "D4") (pin "10") (pinfunction "10_10") (pintype "unspecified"))
      (node (ref "R17") (pin "2") (pinfunction "2_2") (pintype "input"))
      (node (ref "U12") (pin "59") (pinfunction "PB7_59") (pintype "unspecified"))
      (node (ref "U5") (pin "7") (pinfunction "SDA_7") (pintype "unspecified"))
      (node (ref "U9") (pin "3") (pinfunction "SDA_3") (pintype "unspecified"))
    )
    (net (code "30") (name "I2C3_SCL") (class "Default")
      (node (ref "CN2") (pin "6") (pinfunction "6_6") (pintype "unspecified"))
      (node (ref "D4") (pin "5") (pinfunction "5_5") (pintype "unspecified"))
      (node (ref "D4") (pin "6") (pinfunction "6_6") (pintype "unspecified"))
      (node (ref "R20") (pin "2") (pinfunction "2_2") (pintype "input"))
      (node (ref "U12") (pin "8") (pinfunction "PC0_8") (pintype "unspecified"))
    )
    (net (code "31") (name "I2C3_SDA") (class "Default")
      (node (ref "CN2") (pin "5") (pinfunction "5_5") (pintype "unspecified"))
      (node (ref "D4") (pin "4") (pinfunction "4_4") (pintype "unspecified"))
      (node (ref "D4") (pin "7") (pinfunction "7_7") (pintype "unspecified"))
      (node (ref "R21") (pin "2") (pinfunction "2_2") (pintype "input"))
      (node (ref "U12") (pin "9") (pinfunction "PC1_9") (pintype "unspecified"))
    )
    (net (code "32") (name "IREF") (class "Default")
      (node (ref "FPC1") (pin "8") (pinfunction "8_8") (pintype "input"))
      (node (ref "R14") (pin "2") (pinfunction "2_2") (pintype "input"))
    )
    (net (code "33") (name "IRQ_I2C") (class "Default")
      (node (ref "R11") (pin "1") (pinfunction "1_1") (pintype "input"))
      (node (ref "U12") (pin "2") (pinfunction "PC13_2") (pintype "unspecified"))
      (node (ref "U5") (pin "3") (pinfunction "INT_3") (pintype "unspecified"))
    )
    (net (code "34") (name "IRQ_NEXT") (class "Default")
      (node (ref "U12") (pin "30") (pinfunction "PB12_30") (pintype "unspecified"))
      (node (ref "U14") (pin "12") (pinfunction "6Y_12") (pintype "unspecified"))
    )
    (net (code "35") (name "IRQ_PREV") (class "Default")
      (node (ref "U12") (pin "28") (pinfunction "PB2_28") (pintype "unspecified"))
      (node (ref "U14") (pin "8") (pinfunction "4Y_8") (pintype "unspecified"))
    )
    (net (code "36") (name "IRQ_SELECT") (class "Default")
      (node (ref "U12") (pin "29") (pinfunction "PB10_29") (pintype "unspecified"))
      (node (ref "U14") (pin "10") (pinfunction "5Y_10") (pintype "unspecified"))
    )
    (net (code "37") (name "LED0") (class "Default")
      (node (ref "R38") (pin "1") (pinfunction "1_1") (pintype "input"))
      (node (ref "U12") (pin "10") (pinfunction "PC2_10") (pintype "unspecified"))
    )
    (net (code "38") (name "Net-(C38-Pad2)") (class "Default")
      (node (ref "C38") (pin "2") (pinfunction "2_2") (pintype "input"))
      (node (ref "R27") (pin "2") (pinfunction "2_2") (pintype "input"))
      (node (ref "USBC1") (pin "0") (pinfunction "SH_0") (pintype "input"))
    )
    (net (code "39") (name "Net-(LED1-K)") (class "Default")
      (node (ref "LED1") (pin "1") (pinfunction "K_1") (pintype "input"))
      (node (ref "R38") (pin "2") (pinfunction "2_2") (pintype "input"))
    )
    (net (code "40") (name "Net-(Q1-G)") (class "Default")
      (node (ref "Q1") (pin "1") (pinfunction "G_1") (pintype "unspecified"))
      (node (ref "R26") (pin "2") (pinfunction "2_2") (pintype "input"))
      (node (ref "R37") (pin "2") (pinfunction "2_2") (pintype "input"))
    )
    (net (code "41") (name "Net-(U1-DAT0)") (class "Default")
      (node (ref "R1") (pin "2") (pinfunction "2_2") (pintype "input"))
      (node (ref "U1") (pin "7") (pinfunction "DAT0_7") (pintype "unspecified"))
    )
    (net (code "42") (name "Net-(U3-CANH)") (class "Default")
      (node (ref "L1") (pin "1") (pinfunction "1_1") (pintype "unspecified"))
      (node (ref "U3") (pin "13") (pinfunction "CANH_13") (pintype "unspecified"))
    )
    (net (code "43") (name "Net-(U3-CANL)") (class "Default")
      (node (ref "L1") (pin "2") (pinfunction "2_2") (pintype "unspecified"))
      (node (ref "U3") (pin "12") (pinfunction "CANL_12") (pintype "unspecified"))
    )
    (net (code "44") (name "Net-(U3-RXD)") (class "Default")
      (node (ref "R5") (pin "2") (pinfunction "2_2") (pintype "input"))
      (node (ref "U3") (pin "5") (pinfunction "RXD_5") (pintype "unspecified"))
    )
    (net (code "45") (name "Net-(U6-DO)") (class "Default")
      (node (ref "R13") (pin "2") (pinfunction "2_2") (pintype "input"))
      (node (ref "U6") (pin "2") (pinfunction "DO_2") (pintype "unspecified"))
    )
    (net (code "46") (name "Net-(U7-SW)") (class "Default")
      (node (ref "L4") (pin "2") (pinfunction "2_2") (pintype "unspecified"))
      (node (ref "U7") (pin "1") (pinfunction "SW_1") (pintype "unspecified"))
    )
    (net (code "47") (name "Net-(U8-CLK)") (class "Default")
      (node (ref "RN1") (pin "3") (pinfunction "3_3") (pintype "input"))
      (node (ref "U8") (pin "6") (pinfunction "CLK_6") (pintype "input"))
    )
    (net (code "48") (name "Net-(U8-CS#)") (class "Default")
      (node (ref "R18") (pin "2") (pinfunction "2_2") (pintype "input"))
      (node (ref "RN2") (pin "5") (pinfunction "5_5") (pintype "input"))
      (node (ref "U8") (pin "1") (pinfunction "CS#_1") (pintype "input"))
    )
    (net (code "49") (name "Net-(U8-DI)") (class "Default")
      (node (ref "RN1") (pin "2") (pinfunction "2_2") (pintype "input"))
      (node (ref "U8") (pin "5") (pinfunction "DI_5") (pintype "input"))
    )
    (net (code "50") (name "Net-(U8-DO)") (class "Default")
      (node (ref "RN2") (pin "6") (pinfunction "6_6") (pintype "input"))
      (node (ref "U8") (pin "2") (pinfunction "DO_2") (pintype "input"))
    )
    (net (code "51") (name "Net-(U8-IO2)") (class "Default")
      (node (ref "RN2") (pin "7") (pinfunction "7_7") (pintype "input"))
      (node (ref "U8") (pin "3") (pinfunction "IO2_3") (pintype "input"))
    )
    (net (code "52") (name "Net-(U8-IO3)") (class "Default")
      (node (ref "RN1") (pin "4") (pinfunction "4_4") (pintype "input"))
      (node (ref "U8") (pin "7") (pinfunction "IO3_7") (pintype "input"))
    )
    (net (code "53") (name "Net-(U12-PA8)") (class "Default")
      (node (ref "RN3") (pin "1") (pinfunction "1_1") (pintype "input"))
      (node (ref "U12") (pin "41") (pinfunction "PA8_41") (pintype "unspecified"))
    )
    (net (code "54") (name "Net-(U12-PA9)") (class "Default")
      (node (ref "RN3") (pin "2") (pinfunction "2_2") (pintype "input"))
      (node (ref "U12") (pin "42") (pinfunction "PA9_42") (pintype "unspecified"))
    )
    (net (code "55") (name "Net-(U12-PA10)") (class "Default")
      (node (ref "RN3") (pin "3") (pinfunction "3_3") (pintype "input"))
      (node (ref "U12") (pin "43") (pinfunction "PA10_43") (pintype "unspecified"))
    )
    (net (code "56") (name "Net-(U12-PA11)") (class "Default")
      (node (ref "RN3") (pin "4") (pinfunction "4_4") (pintype "input"))
      (node (ref "U12") (pin "44") (pinfunction "PA11_44") (pintype "unspecified"))
    )
    (net (code "57") (name "Net-(U12-PB9)") (class "Default")
      (node (ref "R19") (pin "1") (pinfunction "1_1") (pintype "input"))
      (node (ref "U12") (pin "62") (pinfunction "PB9_62") (pintype "unspecified"))
    )
    (net (code "58") (name "Net-(U13-A1)") (class "Default")
      (node (ref "RN5") (pin "7") (pinfunction "7_7") (pintype "input"))
      (node (ref "U13") (pin "3") (pinfunction "A1_3") (pintype "unspecified"))
    )
    (net (code "59") (name "Net-(U13-A2)") (class "Default")
      (node (ref "RN5") (pin "8") (pinfunction "8_8") (pintype "input"))
      (node (ref "U13") (pin "4") (pinfunction "A2_4") (pintype "unspecified"))
    )
    (net (code "60") (name "Net-(U13-A3)") (class "Default")
      (node (ref "RN4") (pin "5") (pinfunction "5_5") (pintype "input"))
      (node (ref "U13") (pin "5") (pinfunction "A3_5") (pintype "unspecified"))
    )
    (net (code "61") (name "Net-(U13-A4)") (class "Default")
      (node (ref "RN4") (pin "6") (pinfunction "6_6") (pintype "input"))
      (node (ref "U13") (pin "6") (pinfunction "A4_6") (pintype "unspecified"))
    )
    (net (code "62") (name "Net-(U13-B1)") (class "Default")
      (node (ref "R34") (pin "1") (pinfunction "1_1") (pintype "input"))
      (node (ref "RN7") (pin "4") (pinfunction "4_4") (pintype "input"))
      (node (ref "U13") (pin "14") (pinfunction "B1_14") (pintype "unspecified"))
    )
    (net (code "63") (name "Net-(U13-B2)") (class "Default")
      (node (ref "R28") (pin "1") (pinfunction "1_1") (pintype "input"))
      (node (ref "RN7") (pin "3") (pinfunction "3_3") (pintype "input"))
      (node (ref "U13") (pin "13") (pinfunction "B2_13") (pintype "unspecified"))
    )
    (net (code "64") (name "Net-(U13-B3)") (class "Default")
      (node (ref "R32") (pin "1") (pinfunction "1_1") (pintype "input"))
      (node (ref "RN7") (pin "2") (pinfunction "2_2") (pintype "input"))
      (node (ref "U13") (pin "12") (pinfunction "B3_12") (pintype "unspecified"))
    )
    (net (code "65") (name "Net-(U13-B4)") (class "Default")
      (node (ref "R33") (pin "1") (pinfunction "1_1") (pintype "input"))
      (node (ref "RN7") (pin "1") (pinfunction "1_1") (pintype "input"))
      (node (ref "U13") (pin "11") (pinfunction "B4_11") (pintype "unspecified"))
    )
    (net (code "66") (name "Net-(U13-DIR1)") (class "Default")
      (node (ref "RN5") (pin "5") (pinfunction "5_5") (pintype "input"))
      (node (ref "U13") (pin "1") (pinfunction "DIR1_1") (pintype "unspecified"))
    )
    (net (code "67") (name "Net-(U13-DIR2)") (class "Default")
      (node (ref "RN5") (pin "6") (pinfunction "6_6") (pintype "input"))
      (node (ref "U13") (pin "2") (pinfunction "DIR2_2") (pintype "unspecified"))
    )
    (net (code "68") (name "Net-(U13-DIR3)") (class "Default")
      (node (ref "RN4") (pin "7") (pinfunction "7_7") (pintype "input"))
      (node (ref "U13") (pin "7") (pinfunction "DIR3_7") (pintype "unspecified"))
    )
    (net (code "69") (name "Net-(U13-DIR4)") (class "Default")
      (node (ref "RN4") (pin "8") (pinfunction "8_8") (pintype "input"))
      (node (ref "U13") (pin "8") (pinfunction "DIR4_8") (pintype "unspecified"))
    )
    (net (code "70") (name "Net-(U14-1Y)") (class "Default")
      (node (ref "R29") (pin "1") (pinfunction "1_1") (pintype "input"))
      (node (ref "U14") (pin "2") (pinfunction "1Y_2") (pintype "unspecified"))
    )
    (net (code "71") (name "Net-(U14-2Y)") (class "Default")
      (node (ref "R30") (pin "1") (pinfunction "1_1") (pintype "input"))
      (node (ref "U14") (pin "4") (pinfunction "2Y_4") (pintype "unspecified"))
    )
    (net (code "72") (name "Net-(U14-3Y)") (class "Default")
      (node (ref "R31") (pin "1") (pinfunction "1_1") (pintype "input"))
      (node (ref "U14") (pin "6") (pinfunction "3Y_6") (pintype "unspecified"))
    )
    (net (code "73") (name "Net-(U14-4A)") (class "Default")
      (node (ref "C41") (pin "1") (pinfunction "1_1") (pintype "unspecified"))
      (node (ref "R31") (pin "2") (pinfunction "2_2") (pintype "input"))
      (node (ref "U14") (pin "9") (pinfunction "4A_9") (pintype "unspecified"))
    )
    (net (code "74") (name "Net-(U14-5A)") (class "Default")
      (node (ref "C40") (pin "1") (pinfunction "1_1") (pintype "unspecified"))
      (node (ref "R30") (pin "2") (pinfunction "2_2") (pintype "input"))
      (node (ref "U14") (pin "11") (pinfunction "5A_11") (pintype "unspecified"))
    )
    (net (code "75") (name "Net-(U14-6A)") (class "Default")
      (node (ref "C39") (pin "1") (pinfunction "1_1") (pintype "unspecified"))
      (node (ref "R29") (pin "2") (pinfunction "2_2") (pintype "input"))
      (node (ref "U14") (pin "13") (pinfunction "6A_13") (pintype "unspecified"))
    )
    (net (code "76") (name "Net-(U15-A1)") (class "Default")
      (node (ref "RN6") (pin "1") (pinfunction "1_1") (pintype "input"))
      (node (ref "U15") (pin "3") (pinfunction "A1_3") (pintype "unspecified"))
    )
    (net (code "77") (name "Net-(U15-A2)") (class "Default")
      (node (ref "RN6") (pin "2") (pinfunction "2_2") (pintype "input"))
      (node (ref "U15") (pin "4") (pinfunction "A2_4") (pintype "unspecified"))
    )
    (net (code "78") (name "Net-(U15-A3)") (class "Default")
      (node (ref "RN6") (pin "3") (pinfunction "3_3") (pintype "input"))
      (node (ref "U15") (pin "5") (pinfunction "A3_5") (pintype "unspecified"))
    )
    (net (code "79") (name "Net-(U15-A4)") (class "Default")
      (node (ref "RN6") (pin "4") (pinfunction "4_4") (pintype "input"))
      (node (ref "U15") (pin "6") (pinfunction "A4_6") (pintype "unspecified"))
    )
    (net (code "80") (name "Net-(U15-B1)") (class "Default")
      (node (ref "RN8") (pin "4") (pinfunction "4_4") (pintype "input"))
      (node (ref "U15") (pin "14") (pinfunction "B1_14") (pintype "unspecified"))
    )
    (net (code "81") (name "Net-(U15-B2)") (class "Default")
      (node (ref "R36") (pin "1") (pinfunction "1_1") (pintype "input"))
      (node (ref "RN8") (pin "3") (pinfunction "3_3") (pintype "input"))
      (node (ref "U15") (pin "13") (pinfunction "B2_13") (pintype "unspecified"))
    )
    (net (code "82") (name "Net-(U15-B3)") (class "Default")
      (node (ref "R35") (pin "1") (pinfunction "1_1") (pintype "input"))
      (node (ref "RN8") (pin "2") (pinfunction "2_2") (pintype "input"))
      (node (ref "U15") (pin "12") (pinfunction "B3_12") (pintype "unspecified"))
    )
    (net (code "83") (name "Net-(U15-B4)") (class "Default")
      (node (ref "RN8") (pin "1") (pinfunction "1_1") (pintype "input"))
      (node (ref "U15") (pin "11") (pinfunction "B4_11") (pintype "unspecified"))
    )
    (net (code "84") (name "Net-(USBC1-CC1)") (class "Default")
      (node (ref "R25") (pin "2") (pinfunction "2_2") (pintype "input"))
      (node (ref "USBC1") (pin "A5") (pinfunction "CC1_A5") (pintype "input"))
    )
    (net (code "85") (name "Net-(USBC1-CC2)") (class "Default")
      (node (ref "R22") (pin "1") (pinfunction "1_1") (pintype "input"))
      (node (ref "USBC1") (pin "B5") (pinfunction "CC2_B5") (pintype "input"))
    )
    (net (code "86") (name "OSC32_IN") (class "Default")
      (node (ref "C28") (pin "2") (pinfunction "2_2") (pintype "input"))
      (node (ref "U12") (pin "3") (pinfunction "PC14_3") (pintype "unspecified"))
      (node (ref "X1") (pin "1") (pinfunction "1_1") (pintype "input"))
    )
    (net (code "87") (name "OSC32_OUT") (class "Default")
      (node (ref "C27") (pin "2") (pinfunction "2_2") (pintype "input"))
      (node (ref "U12") (pin "4") (pinfunction "PC15_4") (pintype "unspecified"))
      (node (ref "X1") (pin "2") (pinfunction "2_2") (pintype "input"))
    )
    (net (code "88") (name "OSC_IN") (class "Default")
      (node (ref "C30") (pin "1") (pinfunction "1_1") (pintype "input"))
      (node (ref "U12") (pin "5") (pinfunction "PF0_5") (pintype "unspecified"))
      (node (ref "X2") (pin "3") (pinfunction "3_3") (pintype "input"))
    )
    (net (code "89") (name "OSC_OUT") (class "Default")
      (node (ref "C33") (pin "2") (pinfunction "2_2") (pintype "input"))
      (node (ref "U12") (pin "6") (pinfunction "PF1_6") (pintype "unspecified"))
      (node (ref "X2") (pin "1") (pinfunction "1_1") (pintype "input"))
    )
    (net (code "90") (name "PA0") (class "Default")
      (node (ref "RN4") (pin "1") (pinfunction "1_1") (pintype "input"))
      (node (ref "U12") (pin "14") (pinfunction "PA0_14") (pintype "unspecified"))
    )
    (net (code "91") (name "PA1") (class "Default")
      (node (ref "RN4") (pin "2") (pinfunction "2_2") (pintype "input"))
      (node (ref "U12") (pin "15") (pinfunction "PA1_15") (pintype "unspecified"))
    )
    (net (code "92") (name "PA4") (class "Default")
      (node (ref "RN5") (pin "1") (pinfunction "1_1") (pintype "input"))
      (node (ref "U12") (pin "20") (pinfunction "PA4_20") (pintype "unspecified"))
    )
    (net (code "93") (name "PA5") (class "Default")
      (node (ref "RN5") (pin "2") (pinfunction "2_2") (pintype "input"))
      (node (ref "U12") (pin "21") (pinfunction "PA5_21") (pintype "unspecified"))
    )
    (net (code "94") (name "PA6") (class "Default")
      (node (ref "RN5") (pin "3") (pinfunction "3_3") (pintype "input"))
      (node (ref "U12") (pin "22") (pinfunction "PA6_22") (pintype "unspecified"))
    )
    (net (code "95") (name "PA7") (class "Default")
      (node (ref "RN5") (pin "4") (pinfunction "4_4") (pintype "input"))
      (node (ref "U12") (pin "23") (pinfunction "PA7_23") (pintype "unspecified"))
    )
    (net (code "96") (name "PB1") (class "Default")
      (node (ref "TP1") (pin "1") (pinfunction "TEST_PAD1_1") (pintype "input"))
      (node (ref "U12") (pin "27") (pinfunction "PB1_27") (pintype "unspecified"))
    )
    (net (code "97") (name "QSPI_CS") (class "Default")
      (node (ref "RN2") (pin "4") (pinfunction "4_4") (pintype "input"))
      (node (ref "U12") (pin "52") (pinfunction "PC11_52") (pintype "unspecified"))
    )
    (net (code "98") (name "QSPI_IO0") (class "Default")
      (node (ref "RN1") (pin "7") (pinfunction "7_7") (pintype "input"))
      (node (ref "U12") (pin "57") (pinfunction "PB5_57") (pintype "unspecified"))
    )
    (net (code "99") (name "QSPI_IO1") (class "Default")
      (node (ref "RN2") (pin "3") (pinfunction "3_3") (pintype "input"))
      (node (ref "U12") (pin "51") (pinfunction "PC10_51") (pintype "unspecified"))
    )
    (net (code "100") (name "QSPI_IO2") (class "Default")
      (node (ref "RN2") (pin "2") (pinfunction "2_2") (pintype "input"))
      (node (ref "U12") (pin "50") (pinfunction "PA15_50") (pintype "unspecified"))
    )
    (net (code "101") (name "QSPI_IO3") (class "Default")
      (node (ref "RN1") (pin "5") (pinfunction "5_5") (pintype "input"))
      (node (ref "U12") (pin "55") (pinfunction "PB3_55") (pintype "unspecified"))
    )
    (net (code "102") (name "QSPI_SCK") (class "Default")
      (node (ref "RN1") (pin "6") (pinfunction "6_6") (pintype "input"))
      (node (ref "U12") (pin "56") (pinfunction "PB4_56") (pintype "unspecified"))
    )
    (net (code "103") (name "RST") (class "Default")
      (node (ref "C35") (pin "2") (pinfunction "2_2") (pintype "input"))
      (node (ref "D8") (pin "2") (pinfunction "A_2") (pintype "input"))
      (node (ref "SW2") (pin "4") (pinfunction "4_4") (pintype "input"))
      (node (ref "U12") (pin "7") (pinfunction "NRST_7") (pintype "unspecified"))
    )
    (net (code "104") (name "RTC") (class "Default")
      (node (ref "R12") (pin "1") (pinfunction "1_1") (pintype "input"))
      (node (ref "TP7") (pin "1") (pinfunction "TEST_PAD1_1") (pintype "input"))
      (node (ref "U5") (pin "1") (pinfunction "FREQ_1") (pintype "unspecified"))
    )
    (net (code "105") (name "SD_CS") (class "Default")
      (node (ref "D2") (pin "1") (pinfunction "1_1") (pintype "unspecified"))
      (node (ref "D2") (pin "10") (pinfunction "10_10") (pintype "unspecified"))
      (node (ref "R6") (pin "1") (pinfunction "1_1") (pintype "input"))
      (node (ref "RN3") (pin "5") (pinfunction "5_5") (pintype "input"))
      (node (ref "U1") (pin "2") (pinfunction "CD/DAT3_2") (pintype "unspecified"))
    )
    (net (code "106") (name "SD_DETECT") (class "Default")
      (node (ref "D3") (pin "5") (pinfunction "5_5") (pintype "unspecified"))
      (node (ref "D3") (pin "6") (pinfunction "6_6") (pintype "unspecified"))
      (node (ref "R3") (pin "1") (pinfunction "1_1") (pintype "input"))
      (node (ref "U1") (pin "Cd") (pinfunction "Cd_Cd") (pintype "unspecified"))
      (node (ref "U12") (pin "40") (pinfunction "PC9_40") (pintype "unspecified"))
    )
    (net (code "107") (name "SD_ON") (class "Default")
      (node (ref "R2") (pin "2") (pinfunction "2_2") (pintype "input"))
      (node (ref "U12") (pin "39") (pinfunction "PC8_39") (pintype "unspecified"))
      (node (ref "U2") (pin "3") (pinfunction "ON_3") (pintype "input"))
    )
    (net (code "108") (name "SERIAL_RXD") (class "Default")
      (node (ref "RN4") (pin "4") (pinfunction "4_4") (pintype "input"))
      (node (ref "U12") (pin "17") (pinfunction "PA3_17") (pintype "unspecified"))
    )
    (net (code "109") (name "SERIAL_TXD") (class "Default")
      (node (ref "RN4") (pin "3") (pinfunction "3_3") (pintype "input"))
      (node (ref "U12") (pin "16") (pinfunction "PA2_16") (pintype "unspecified"))
    )
    (net (code "110") (name "SPI2_CLK") (class "Default")
      (node (ref "D3") (pin "1") (pinfunction "1_1") (pintype "unspecified"))
      (node (ref "D3") (pin "10") (pinfunction "10_10") (pintype "unspecified"))
      (node (ref "FPC1") (pin "4") (pinfunction "4_4") (pintype "input"))
      (node (ref "RN3") (pin "7") (pinfunction "7_7") (pintype "input"))
      (node (ref "U1") (pin "5") (pinfunction "CLX_5") (pintype "unspecified"))
      (node (ref "U6") (pin "6") (pinfunction "CLK_6") (pintype "unspecified"))
    )
    (net (code "111") (name "SPI2_MISO") (class "Default")
      (node (ref "D3") (pin "4") (pinfunction "4_4") (pintype "unspecified"))
      (node (ref "D3") (pin "7") (pinfunction "7_7") (pintype "unspecified"))
      (node (ref "R1") (pin "1") (pinfunction "1_1") (pintype "input"))
      (node (ref "R13") (pin "1") (pinfunction "1_1") (pintype "input"))
      (node (ref "R8") (pin "1") (pinfunction "1_1") (pintype "input"))
      (node (ref "U12") (pin "45") (pinfunction "PA12_45") (pintype "unspecified"))
    )
    (net (code "112") (name "SPI2_MOSI") (class "Default")
      (node (ref "D2") (pin "5") (pinfunction "5_5") (pintype "unspecified"))
      (node (ref "D2") (pin "6") (pinfunction "6_6") (pintype "unspecified"))
      (node (ref "FPC1") (pin "3") (pinfunction "3_3") (pintype "input"))
      (node (ref "R7") (pin "1") (pinfunction "1_1") (pintype "input"))
      (node (ref "RN3") (pin "6") (pinfunction "6_6") (pintype "input"))
      (node (ref "U1") (pin "3") (pinfunction "CMD_3") (pintype "unspecified"))
      (node (ref "U6") (pin "5") (pinfunction "DI_5") (pintype "unspecified"))
    )
    (net (code "113") (name "SW_NEXT") (class "Default")
      (node (ref "D13") (pin "2") (pinfunction "A_2") (pintype "input"))
      (node (ref "R42") (pin "1") (pinfunction "1_1") (pintype "input"))
      (node (ref "SW3") (pin "2") (pinfunction "2_2") (pintype "unspecified"))
      (node (ref "U14") (pin "1") (pinfunction "1A_1") (pintype "unspecified"))
    )
    (net (code "114") (name "SW_PREV") (class "Default")
      (node (ref "D15") (pin "2") (pinfunction "A_2") (pintype "input"))
      (node (ref "R44") (pin "1") (pinfunction "1_1") (pintype "input"))
      (node (ref "SW3") (pin "1") (pinfunction "1_1") (pintype "unspecified"))
      (node (ref "U14") (pin "5") (pinfunction "3A_5") (pintype "unspecified"))
    )
    (net (code "115") (name "SW_SELECT") (class "Default")
      (node (ref "D14") (pin "2") (pinfunction "A_2") (pintype "input"))
      (node (ref "R43") (pin "1") (pinfunction "1_1") (pintype "input"))
      (node (ref "SW3") (pin "T") (pinfunction "T_T") (pintype "unspecified"))
      (node (ref "U14") (pin "3") (pinfunction "2A_3") (pintype "unspecified"))
    )
    (net (code "116") (name "SYS_SWCLK") (class "Default")
      (node (ref "CN3") (pin "5") (pinfunction "5_5") (pintype "unspecified"))
      (node (ref "D9") (pin "1") (pinfunction "1_1") (pintype "unspecified"))
      (node (ref "D9") (pin "10") (pinfunction "10_10") (pintype "unspecified"))
      (node (ref "U12") (pin "49") (pinfunction "PA14_49") (pintype "unspecified"))
    )
    (net (code "117") (name "SYS_SWDIO") (class "Default")
      (node (ref "CN3") (pin "4") (pinfunction "4_4") (pintype "unspecified"))
      (node (ref "D9") (pin "2") (pinfunction "2_2") (pintype "unspecified"))
      (node (ref "D9") (pin "9") (pinfunction "9_9") (pintype "unspecified"))
      (node (ref "U12") (pin "46") (pinfunction "PA13_46") (pintype "unspecified"))
    )
    (net (code "118") (name "T_AUX_RXD") (class "Default")
      (node (ref "CN5") (pin "3") (pinfunction "3_3") (pintype "unspecified"))
      (node (ref "D17") (pin "4") (pinfunction "4_4") (pintype "unspecified"))
      (node (ref "D17") (pin "7") (pinfunction "7_7") (pintype "unspecified"))
      (node (ref "RN8") (pin "7") (pinfunction "7_7") (pintype "input"))
    )
    (net (code "119") (name "T_AUX_TXD") (class "Default")
      (node (ref "CN5") (pin "2") (pinfunction "2_2") (pintype "unspecified"))
      (node (ref "D17") (pin "5") (pinfunction "5_5") (pintype "unspecified"))
      (node (ref "D17") (pin "6") (pinfunction "6_6") (pintype "unspecified"))
      (node (ref "RN8") (pin "8") (pinfunction "8_8") (pintype "input"))
    )
    (net (code "120") (name "T_OE") (class "Default")
      (node (ref "R45") (pin "1") (pinfunction "1_1") (pintype "input"))
      (node (ref "U12") (pin "18") (pinfunction "PF4_18") (pintype "unspecified"))
      (node (ref "U13") (pin "9") (pinfunction "OE#_9") (pintype "unspecified"))
      (node (ref "U15") (pin "9") (pinfunction "OE#_9") (pintype "unspecified"))
    )
    (net (code "121") (name "T_POWER_ON") (class "Default")
      (node (ref "R41") (pin "2") (pinfunction "2_2") (pintype "input"))
      (node (ref "U12") (pin "19") (pinfunction "PF5_19") (pintype "unspecified"))
      (node (ref "U16") (pin "3") (pinfunction "ON_3") (pintype "input"))
    )
    (net (code "122") (name "T_RST") (class "Default")
      (node (ref "CN5") (pin "5") (pinfunction "5_5") (pintype "unspecified"))
      (node (ref "D17") (pin "1") (pinfunction "1_1") (pintype "unspecified"))
      (node (ref "D17") (pin "10") (pinfunction "10_10") (pintype "unspecified"))
      (node (ref "Q1") (pin "3") (pinfunction "D_3") (pintype "unspecified"))
      (node (ref "R46") (pin "2") (pinfunction "2_2") (pintype "input"))
      (node (ref "RN8") (pin "5") (pinfunction "5_5") (pintype "input"))
    )
    (net (code "123") (name "T_RST_IN") (class "Default")
      (node (ref "RN6") (pin "8") (pinfunction "8_8") (pintype "input"))
      (node (ref "U12") (pin "26") (pinfunction "PB0_26") (pintype "unspecified"))
    )
    (net (code "124") (name "T_RST_OUT") (class "Default")
      (node (ref "R26") (pin "1") (pinfunction "1_1") (pintype "input"))
      (node (ref "U12") (pin "32") (pinfunction "PB13_32") (pintype "unspecified"))
    )
    (net (code "125") (name "T_RXD") (class "Default")
      (node (ref "CN4") (pin "3") (pinfunction "3_3") (pintype "unspecified"))
      (node (ref "D12") (pin "4") (pinfunction "4_4") (pintype "unspecified"))
      (node (ref "D12") (pin "7") (pinfunction "7_7") (pintype "unspecified"))
      (node (ref "RN7") (pin "7") (pinfunction "7_7") (pintype "input"))
    )
    (net (code "126") (name "T_SWCLK") (class "Default")
      (node (ref "CN4") (pin "5") (pinfunction "5_5") (pintype "unspecified"))
      (node (ref "D12") (pin "1") (pinfunction "1_1") (pintype "unspecified"))
      (node (ref "D12") (pin "10") (pinfunction "10_10") (pintype "unspecified"))
      (node (ref "RN7") (pin "5") (pinfunction "5_5") (pintype "input"))
    )
    (net (code "127") (name "T_SWDIO") (class "Default")
      (node (ref "CN4") (pin "4") (pinfunction "4_4") (pintype "unspecified"))
      (node (ref "D12") (pin "2") (pinfunction "2_2") (pintype "unspecified"))
      (node (ref "D12") (pin "9") (pinfunction "9_9") (pintype "unspecified"))
      (node (ref "RN7") (pin "6") (pinfunction "6_6") (pintype "input"))
    )
    (net (code "128") (name "T_SWO") (class "Default")
      (node (ref "CN5") (pin "4") (pinfunction "4_4") (pintype "unspecified"))
      (node (ref "D17") (pin "2") (pinfunction "2_2") (pintype "unspecified"))
      (node (ref "D17") (pin "9") (pinfunction "9_9") (pintype "unspecified"))
      (node (ref "RN8") (pin "6") (pinfunction "6_6") (pintype "input"))
    )
    (net (code "129") (name "T_TXD") (class "Default")
      (node (ref "CN4") (pin "2") (pinfunction "2_2") (pintype "unspecified"))
      (node (ref "D12") (pin "5") (pinfunction "5_5") (pintype "unspecified"))
      (node (ref "D12") (pin "6") (pinfunction "6_6") (pintype "unspecified"))
      (node (ref "RN7") (pin "8") (pinfunction "8_8") (pintype "input"))
    )
    (net (code "130") (name "VBAT") (class "Default")
      (node (ref "BT1") (pin "1") (pinfunction "+_1") (pintype "input"))
      (node (ref "BT1") (pin "2") (pinfunction "+_2") (pintype "input"))
      (node (ref "C21") (pin "2") (pinfunction "2_2") (pintype "unspecified"))
      (node (ref "U5") (pin "6") (pinfunction "VBAT_6") (pintype "unspecified"))
    )
    (net (code "131") (name "VBUS") (class "Default")
      (node (ref "C25") (pin "2") (pinfunction "2_2") (pintype "unspecified"))
      (node (ref "U10") (pin "3") (pinfunction "ON_3") (pintype "input"))
      (node (ref "U10") (pin "4") (pinfunction "VIN_4") (pintype "input"))
      (node (ref "U10") (pin "6") (pinfunction "VIN_6") (pintype "input"))
      (node (ref "U11") (pin "2") (pinfunction "2_2") (pintype "unspecified"))
    )
    (net (code "132") (name "VCOMH") (class "Default")
      (node (ref "C14") (pin "2") (pinfunction "2_2") (pintype "unspecified"))
      (node (ref "FPC1") (pin "10") (pinfunction "10_10") (pintype "input"))
    )
    (net (code "133") (name "VFB") (class "Default")
      (node (ref "C9") (pin "1") (pinfunction "1_1") (pintype "input"))
      (node (ref "R10") (pin "1") (pinfunction "1_1") (pintype "input"))
      (node (ref "R4") (pin "2") (pinfunction "2_2") (pintype "input"))
      (node (ref "U4") (pin "5") (pinfunction "FB_5") (pintype "input"))
    )
    (net (code "134") (name "VIO") (class "Default")
      (node (ref "C42") (pin "1") (pinfunction "1_1") (pintype "unspecified"))
      (node (ref "C44") (pin "1") (pinfunction "1_1") (pintype "unspecified"))
      (node (ref "C46") (pin "1") (pinfunction "1_1") (pintype "unspecified"))
      (node (ref "C49") (pin "2") (pinfunction "2_2") (pintype "unspecified"))
      (node (ref "C50") (pin "1") (pinfunction "1_1") (pintype "unspecified"))
      (node (ref "C51") (pin "1") (pinfunction "1_1") (pintype "unspecified"))
      (node (ref "CN4") (pin "1") (pinfunction "1_1") (pintype "unspecified"))
      (node (ref "CN5") (pin "1") (pinfunction "1_1") (pintype "unspecified"))
      (node (ref "D11") (pin "2") (pinfunction "A_2") (pintype "unspecified"))
      (node (ref "D16") (pin "2") (pinfunction "A_2") (pintype "unspecified"))
      (node (ref "R28") (pin "2") (pinfunction "2_2") (pintype "input"))
      (node (ref "R32") (pin "2") (pinfunction "2_2") (pintype "input"))
      (node (ref "R33") (pin "2") (pinfunction "2_2") (pintype "input"))
      (node (ref "R34") (pin "2") (pinfunction "2_2") (pintype "input"))
      (node (ref "R35") (pin "2") (pinfunction "2_2") (pintype "input"))
      (node (ref "R36") (pin "2") (pinfunction "2_2") (pintype "input"))
      (node (ref "R40") (pin "2") (pinfunction "2_2") (pintype "input"))
      (node (ref "R46") (pin "1") (pinfunction "1_1") (pintype "input"))
      (node (ref "TP10") (pin "1") (pinfunction "TEST_PAD1_1") (pintype "input"))
      (node (ref "U13") (pin "15") (pinfunction "VCCB_15") (pintype "unspecified"))
      (node (ref "U15") (pin "15") (pinfunction "VCCB_15") (pintype "unspecified"))
      (node (ref "U16") (pin "1") (pinfunction "VOUT_1") (pintype "input"))
    )
    (net (code "135") (name "VSD") (class "Default")
      (node (ref "C4") (pin "2") (pinfunction "2_2") (pintype "input"))
      (node (ref "C5") (pin "1") (pinfunction "1_1") (pintype "input"))
      (node (ref "TP5") (pin "1") (pinfunction "TEST_PAD1_1") (pintype "input"))
      (node (ref "U1") (pin "4") (pinfunction "VDD_4") (pintype "unspecified"))
      (node (ref "U2") (pin "1") (pinfunction "VOUT_1") (pintype "input"))
    )
    (net (code "136") (name "VSW") (class "Default")
      (node (ref "L3") (pin "1") (pinfunction "1_1") (pintype "unspecified"))
      (node (ref "U4") (pin "3") (pinfunction "SW_3") (pintype "input"))
    )
    (net (code "137") (name "unconnected-(SW1-Pad1)") (class "Default")
      (node (ref "SW1") (pin "1") (pinfunction "1_1") (pintype "input+no_connect"))
    )
    (net (code "138") (name "unconnected-(SW1-Pad2)") (class "Default")
      (node (ref "SW1") (pin "2") (pinfunction "2_2") (pintype "input+no_connect"))
    )
    (net (code "139") (name "unconnected-(SW2-Pad1)") (class "Default")
      (node (ref "SW2") (pin "1") (pinfunction "1_1") (pintype "input+no_connect"))
    )
    (net (code "140") (name "unconnected-(SW2-Pad2)") (class "Default")
      (node (ref "SW2") (pin "2") (pinfunction "2_2") (pintype "input+no_connect"))
    )
    (net (code "141") (name "unconnected-(U1-DAT1-Pad8)") (class "Default")
      (node (ref "U1") (pin "8") (pinfunction "DAT1_8") (pintype "unspecified+no_connect"))
    )
    (net (code "142") (name "unconnected-(U1-DAT2-Pad1)") (class "Default")
      (node (ref "U1") (pin "1") (pinfunction "DAT2_1") (pintype "unspecified+no_connect"))
    )
    (net (code "143") (name "unconnected-(U3-NC-Pad4)") (class "Default")
      (node (ref "U3") (pin "4") (pinfunction "NC_4") (pintype "unspecified+no_connect"))
    )
    (net (code "144") (name "unconnected-(U3-NC-Pad6)") (class "Default")
      (node (ref "U3") (pin "6") (pinfunction "NC_6") (pintype "unspecified+no_connect"))
    )
    (net (code "145") (name "unconnected-(U3-NC-Pad14)") (class "Default")
      (node (ref "U3") (pin "14") (pinfunction "NC_14") (pintype "unspecified+no_connect"))
    )
    (net (code "146") (name "unconnected-(U5-NC-Pad4)") (class "Default")
      (node (ref "U5") (pin "4") (pinfunction "NC_4") (pintype "unspecified+no_connect"))
    )
    (net (code "147") (name "unconnected-(USBC1-SBU1-PadA8)") (class "Default")
      (node (ref "USBC1") (pin "A8") (pinfunction "SBU1_A8") (pintype "input+no_connect"))
    )
    (net (code "148") (name "unconnected-(USBC1-SBU2-PadB8)") (class "Default")
      (node (ref "USBC1") (pin "B8") (pinfunction "SBU2_B8") (pintype "input+no_connect"))
    )
    (net (code "149") (name "unconnected-(USBC1-SH-Pad1)") (class "Default")
      (node (ref "USBC1") (pin "1") (pinfunction "SH_1") (pintype "input+no_connect"))
    )
    (net (code "150") (name "unconnected-(USBC1-SH-Pad2)") (class "Default")
      (node (ref "USBC1") (pin "2") (pinfunction "SH_2") (pintype "input+no_connect"))
    )
    (net (code "151") (name "unconnected-(USBC1-SH-Pad3)") (class "Default")
      (node (ref "USBC1") (pin "3") (pinfunction "SH_3") (pintype "input+no_connect"))
    )
  )
)
